# streams_v05.net
KiCad netlist of a schematic drawn in EAGLE
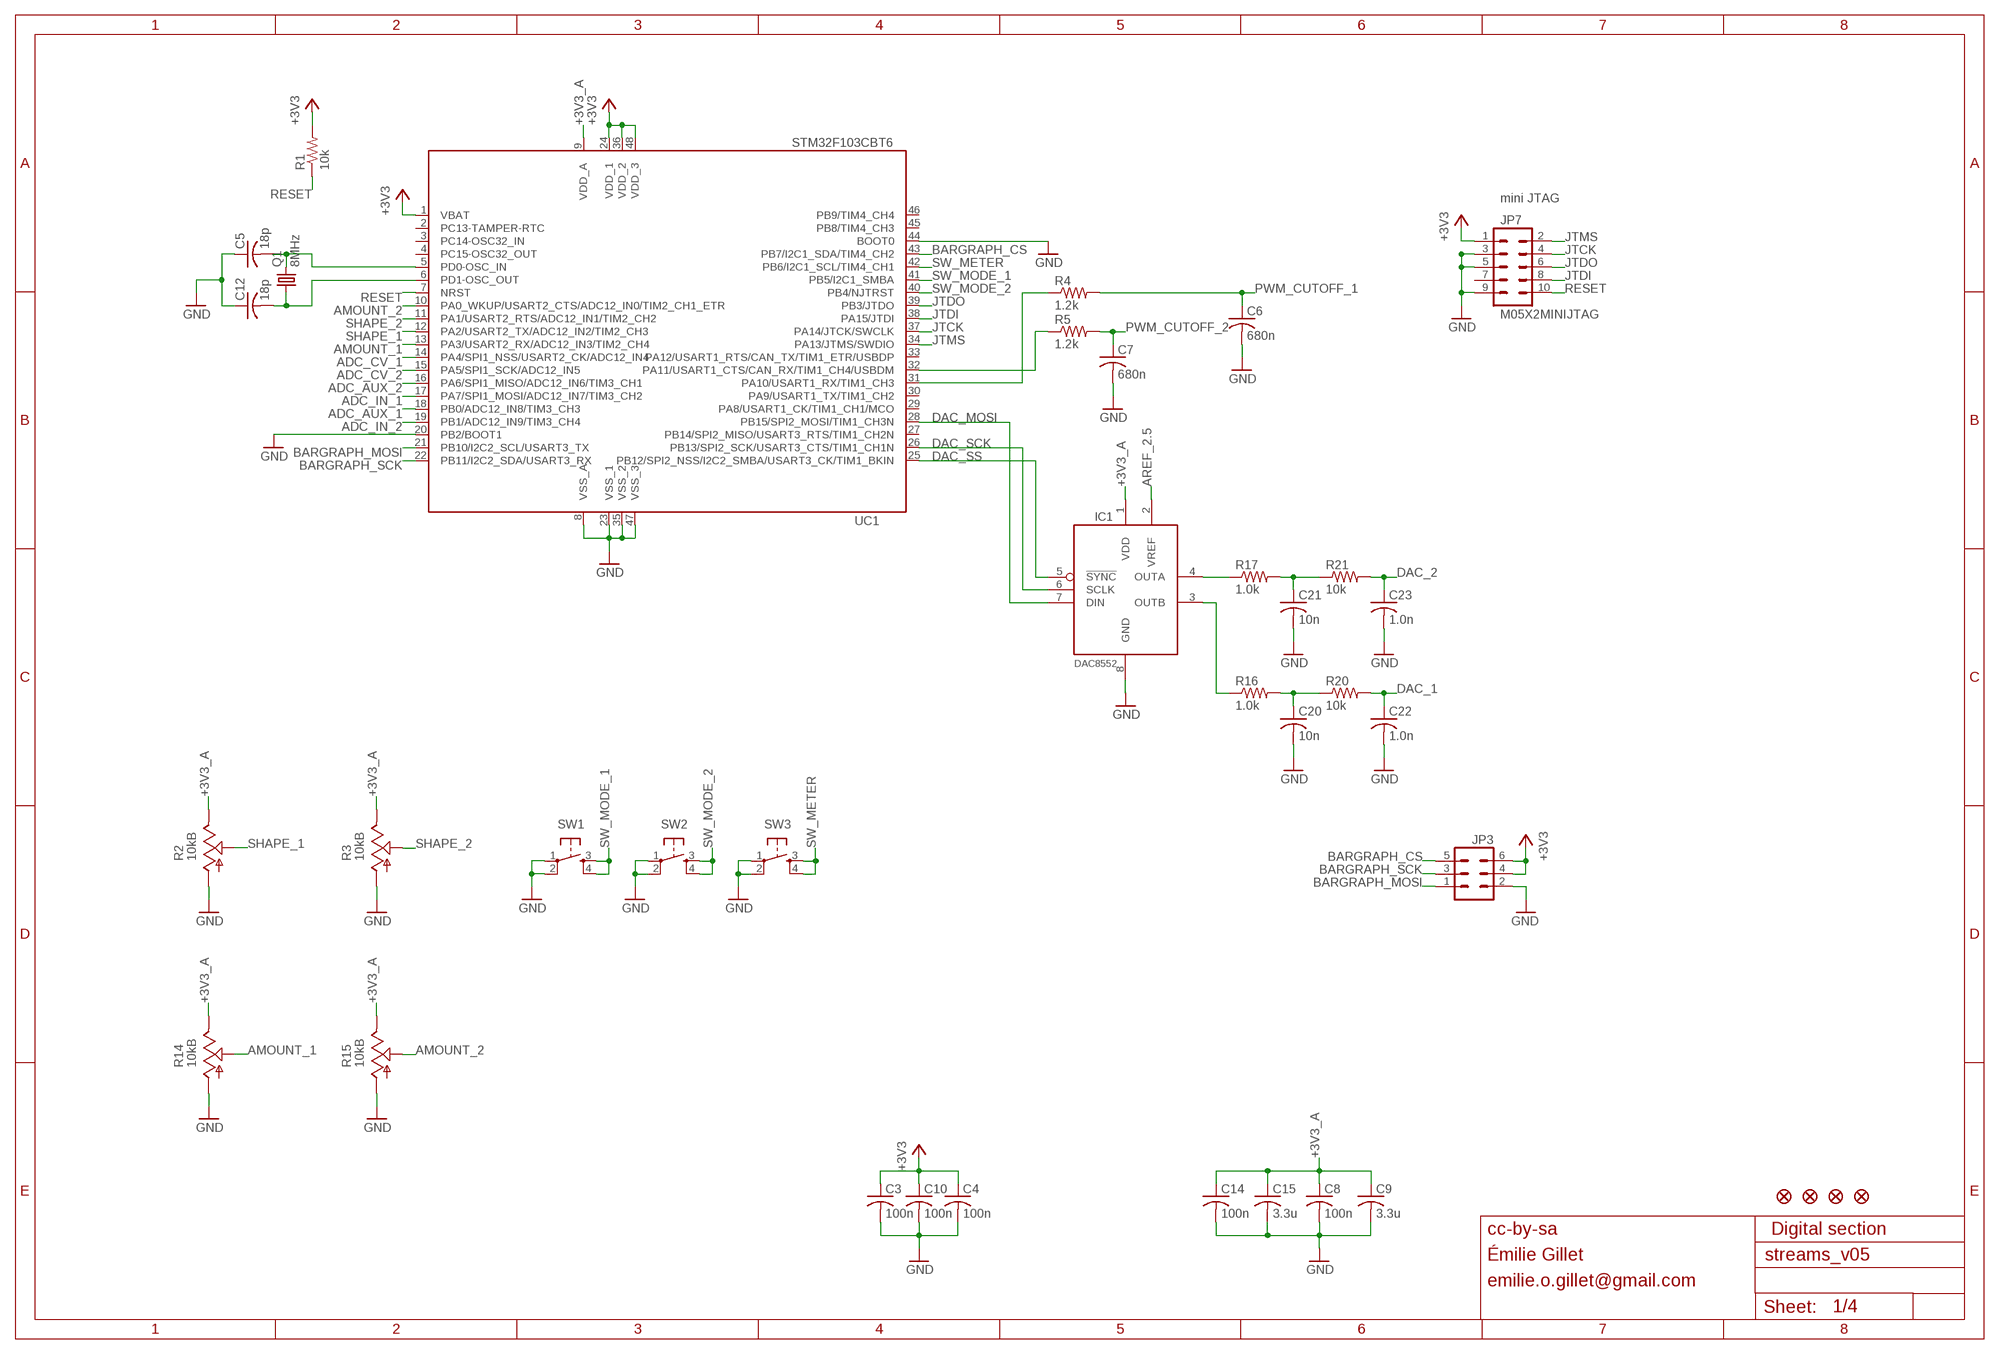
[diagram p0: schematic, sheet 1]
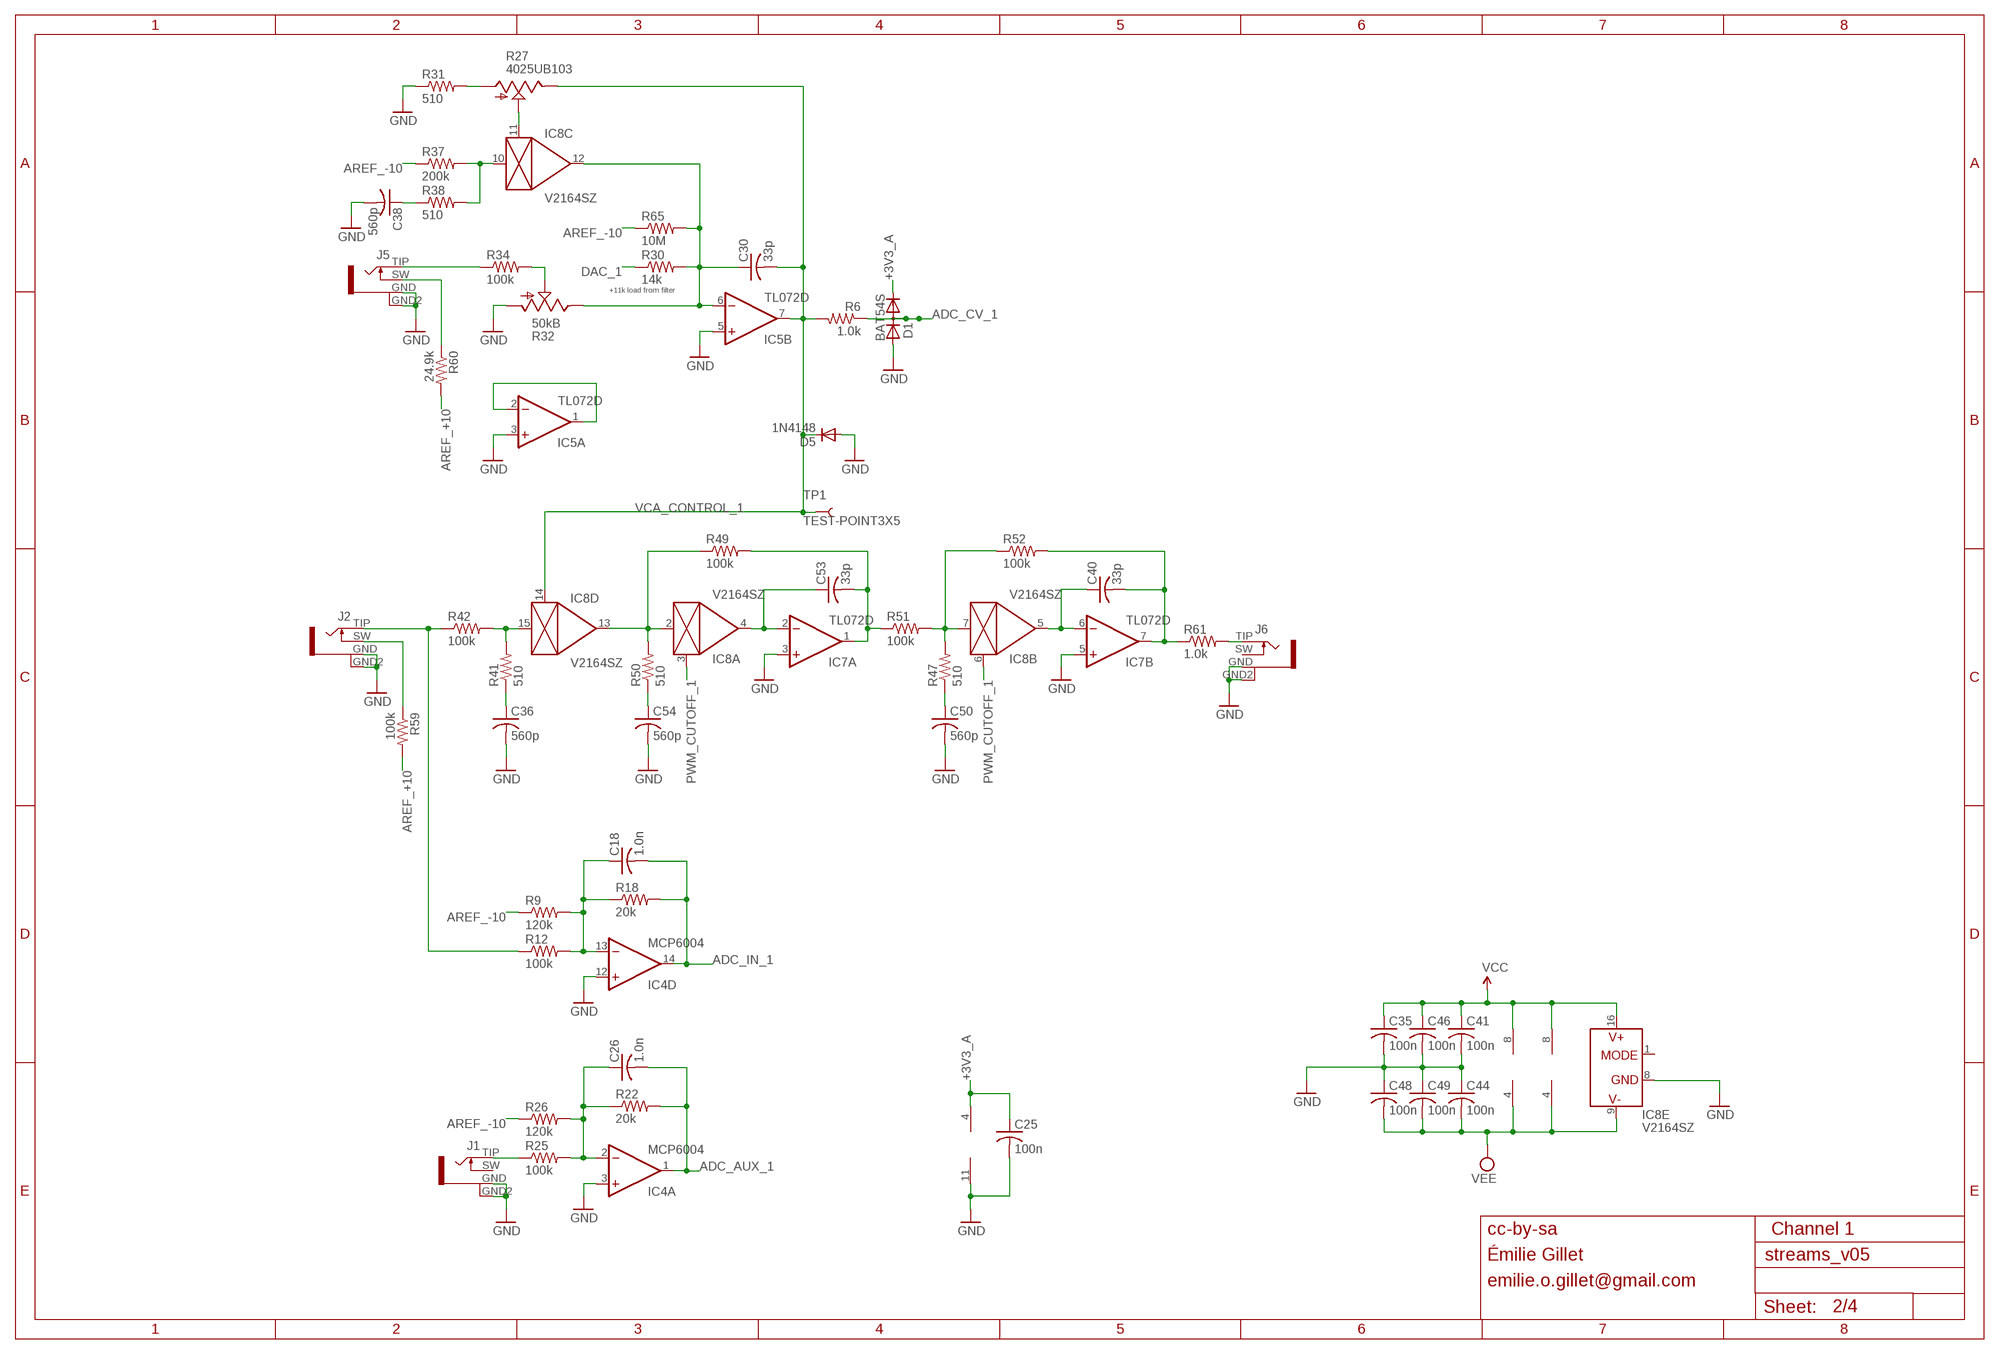
[diagram p1: schematic, sheet 2]
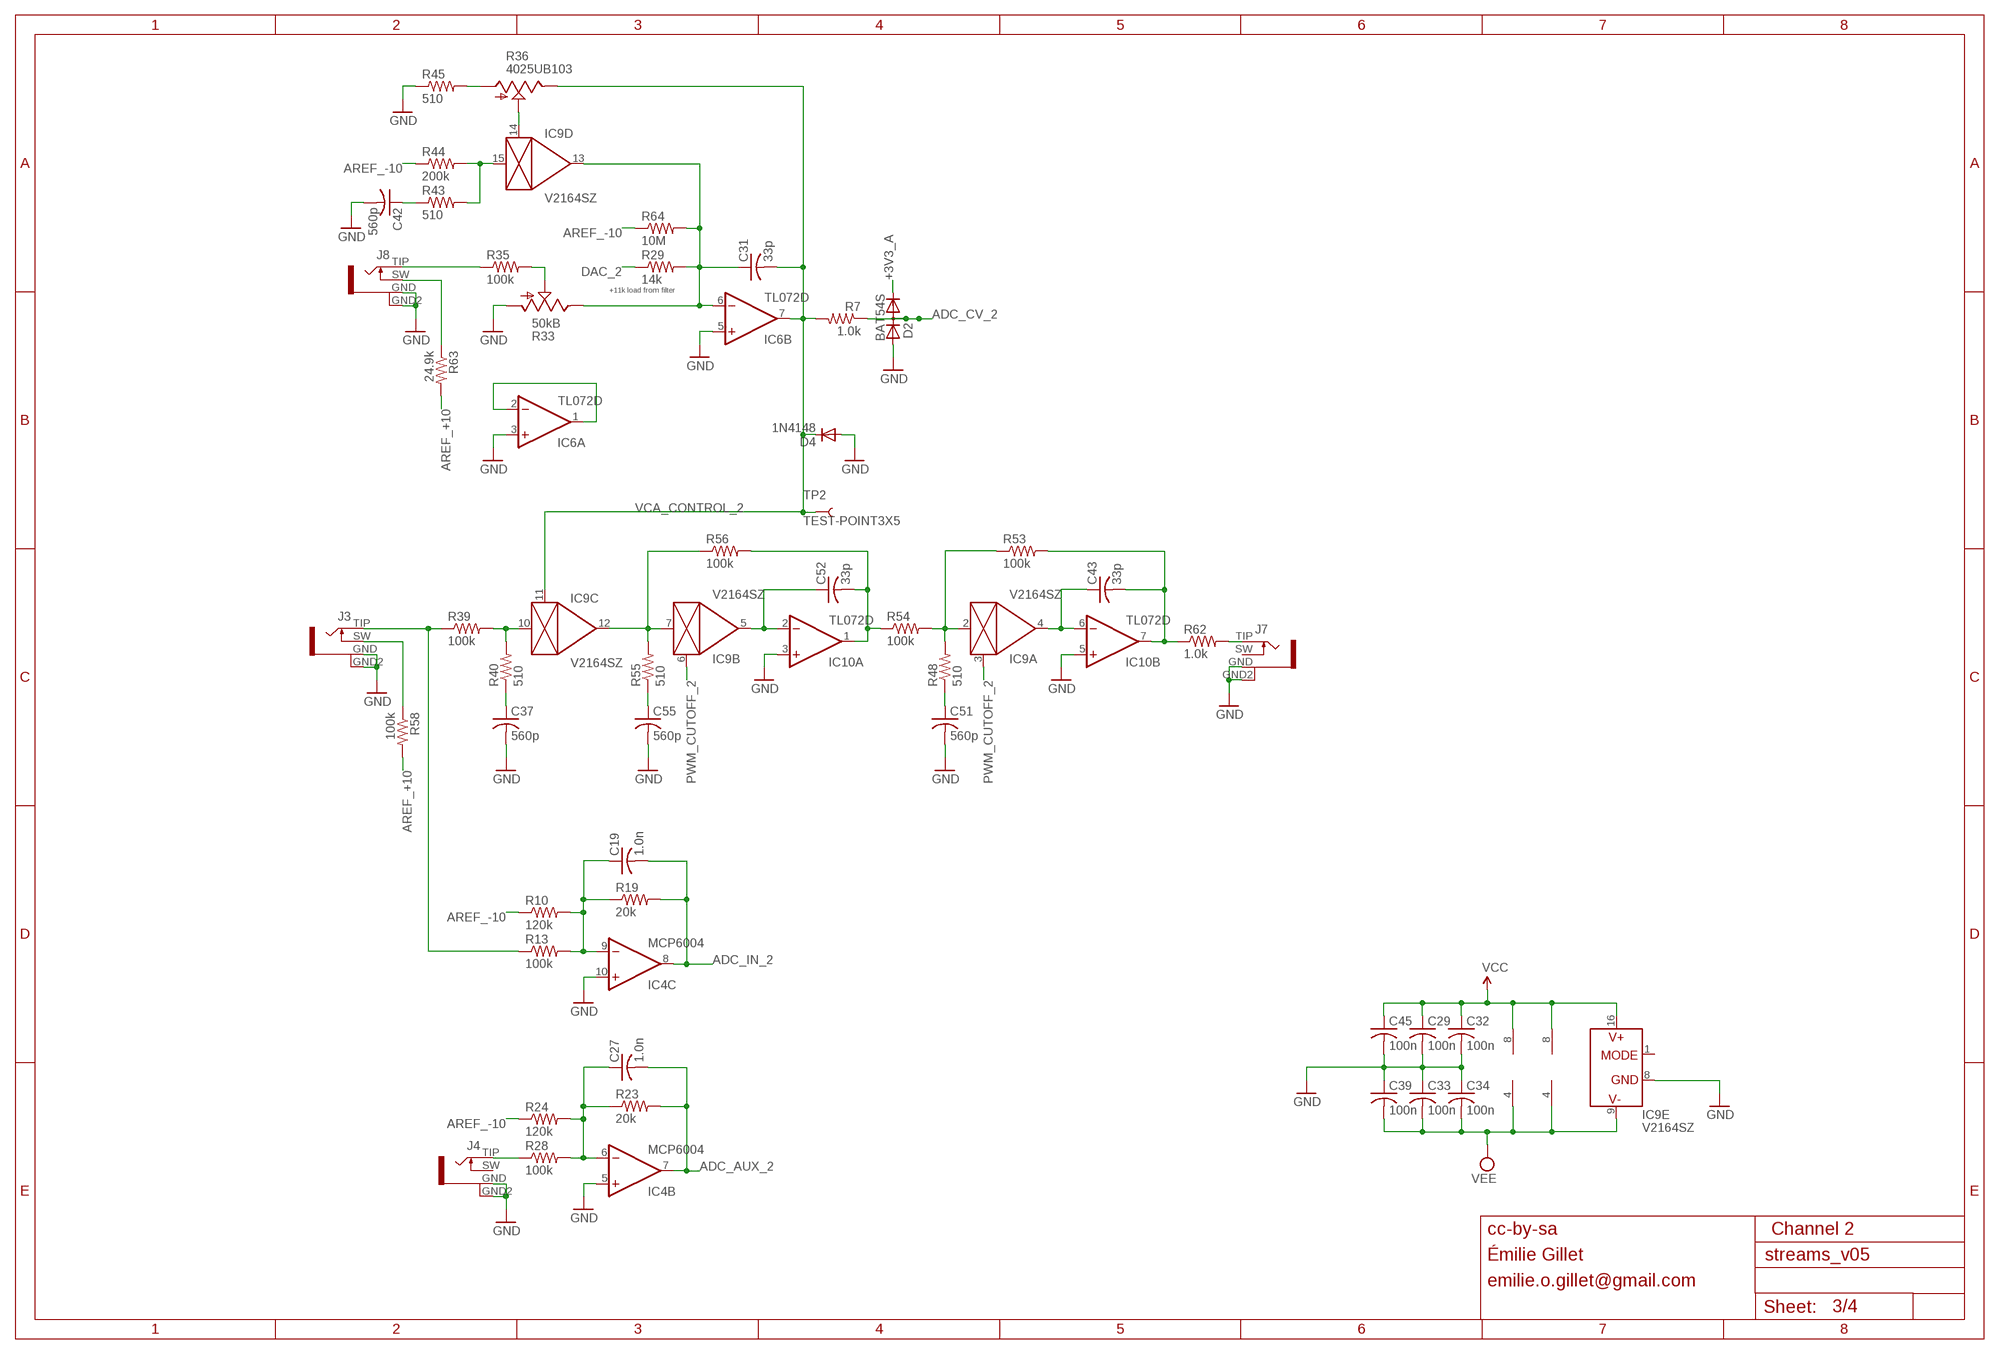
[diagram p2: schematic, sheet 3]
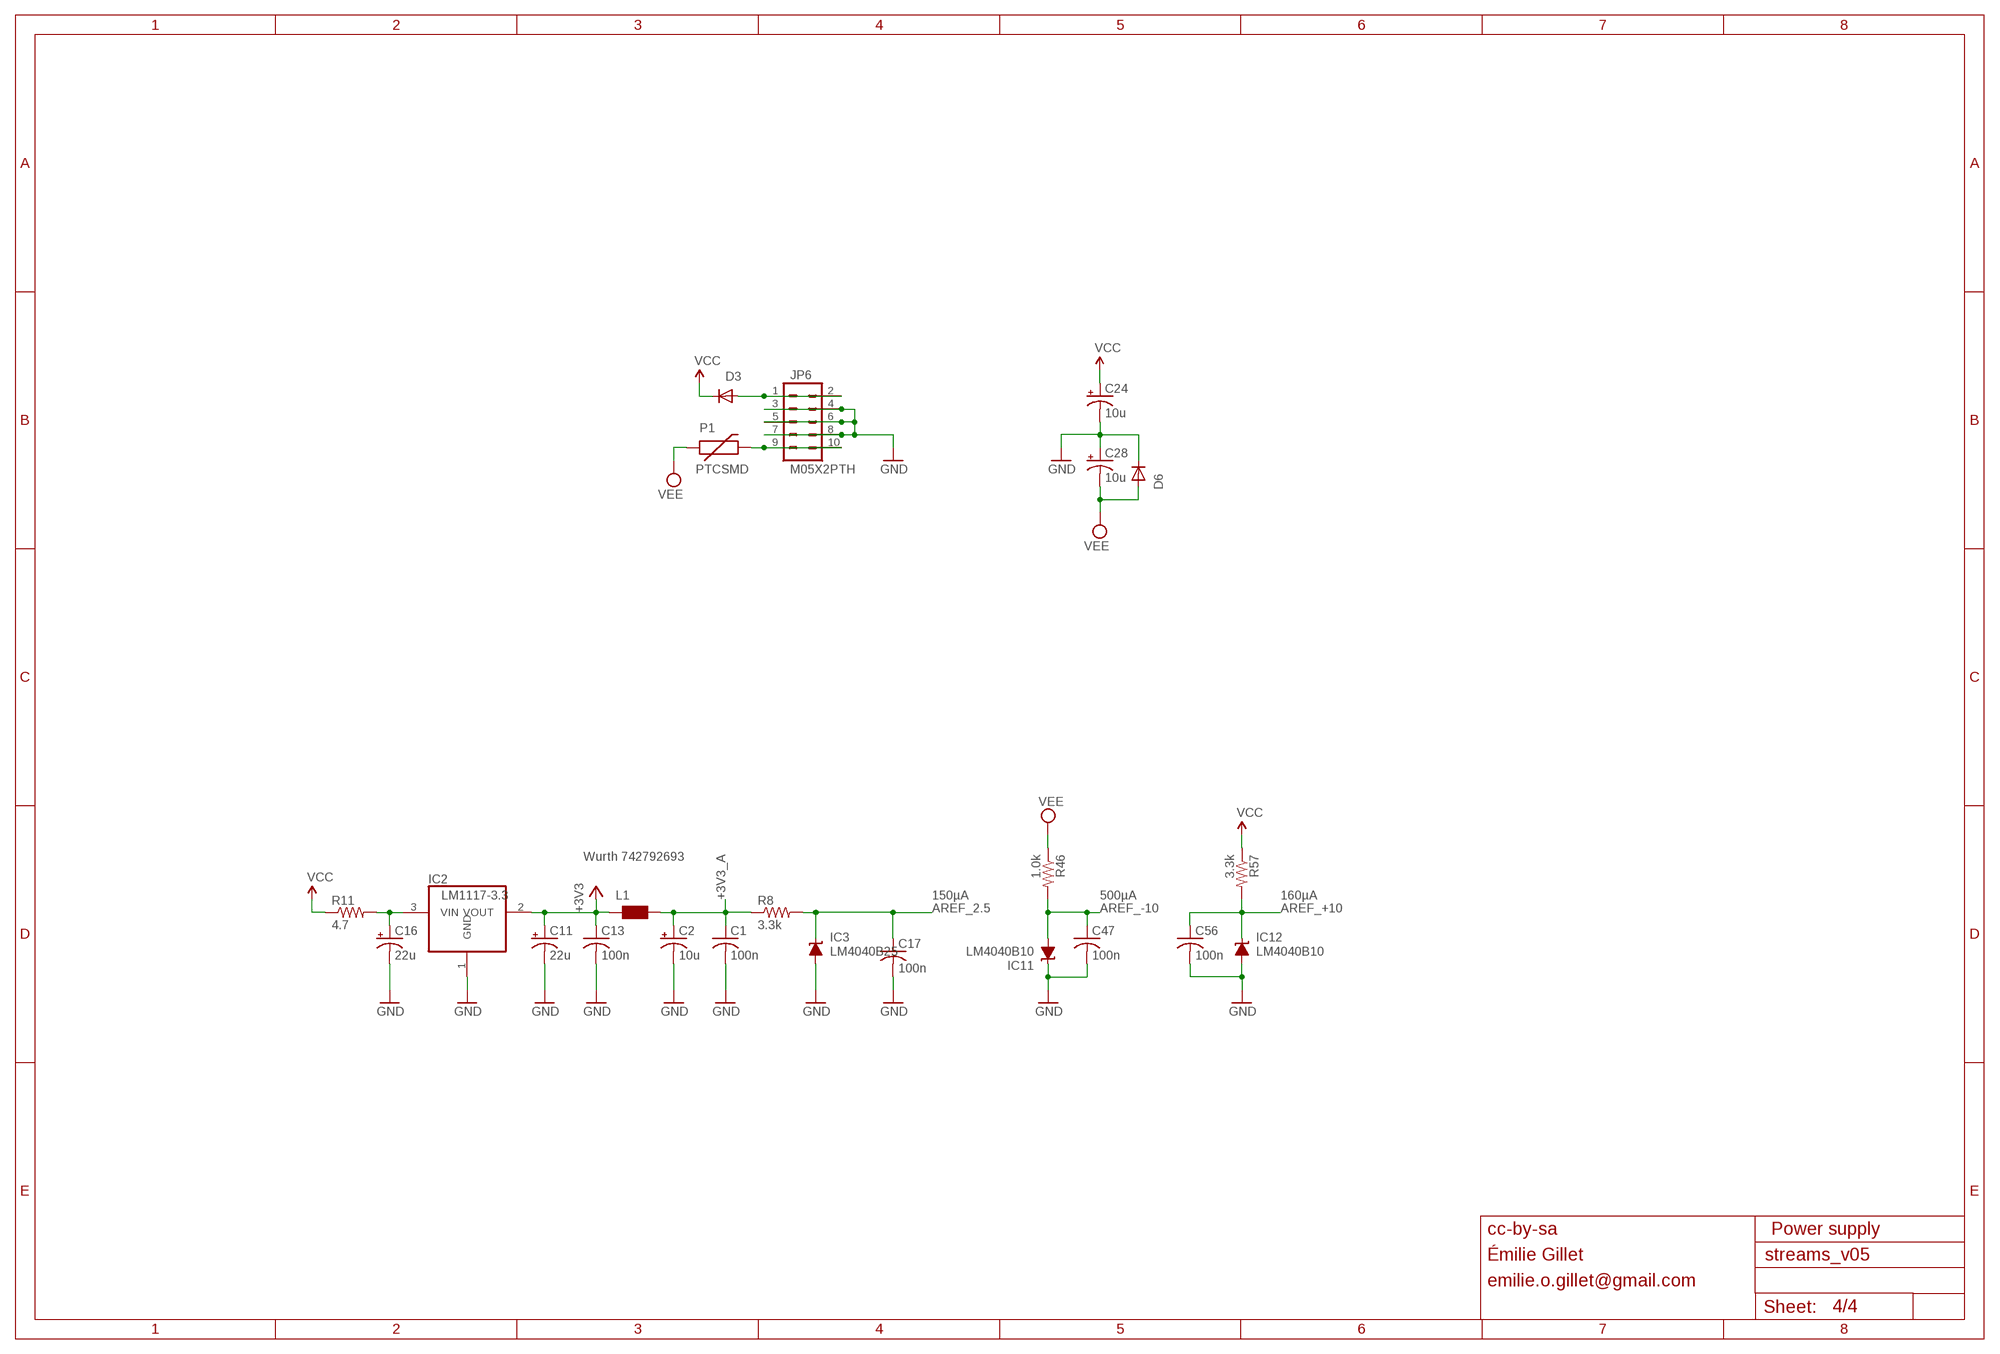
[diagram p3: schematic, sheet 4]

(export (version "E")
  (design (tool "Eeschema 10.0.6"))
  (components
    (comp (ref "C18")
      (value "1.0n")
      (footprint "eagle-import:C0603")
      (libsource (lib "eagle-import") (part "C-USC0603"))
    )
    (comp (ref "C25")
      (value "100n")
      (footprint "eagle-import:C0603")
      (libsource (lib "eagle-import") (part "C-USC0603"))
    )
    (comp (ref "C26")
      (value "1.0n")
      (footprint "eagle-import:C0603")
      (libsource (lib "eagle-import") (part "C-USC0603"))
    )
    (comp (ref "C30")
      (value "33p")
      (footprint "eagle-import:C0603")
      (libsource (lib "eagle-import") (part "C-USC0603"))
    )
    (comp (ref "C35")
      (value "100n")
      (footprint "eagle-import:C0603")
      (libsource (lib "eagle-import") (part "C-USC0603"))
    )
    (comp (ref "C36")
      (value "560p")
      (footprint "eagle-import:C0603")
      (libsource (lib "eagle-import") (part "C-USC0603"))
    )
    (comp (ref "C38")
      (value "560p")
      (footprint "eagle-import:C0603")
      (libsource (lib "eagle-import") (part "C-USC0603"))
    )
    (comp (ref "C40")
      (value "33p")
      (footprint "eagle-import:C0603")
      (libsource (lib "eagle-import") (part "C-USC0603"))
    )
    (comp (ref "C41")
      (value "100n")
      (footprint "eagle-import:C0603")
      (libsource (lib "eagle-import") (part "C-USC0603"))
    )
    (comp (ref "C44")
      (value "100n")
      (footprint "eagle-import:C0603")
      (libsource (lib "eagle-import") (part "C-USC0603"))
    )
    (comp (ref "C46")
      (value "100n")
      (footprint "eagle-import:C0603")
      (libsource (lib "eagle-import") (part "C-USC0603"))
    )
    (comp (ref "C48")
      (value "100n")
      (footprint "eagle-import:C0603")
      (libsource (lib "eagle-import") (part "C-USC0603"))
    )
    (comp (ref "C49")
      (value "100n")
      (footprint "eagle-import:C0603")
      (libsource (lib "eagle-import") (part "C-USC0603"))
    )
    (comp (ref "C50")
      (value "560p")
      (footprint "eagle-import:C0603")
      (libsource (lib "eagle-import") (part "C-USC0603"))
    )
    (comp (ref "C53")
      (value "33p")
      (footprint "eagle-import:C0603")
      (libsource (lib "eagle-import") (part "C-USC0603"))
    )
    (comp (ref "C54")
      (value "560p")
      (footprint "eagle-import:C0603")
      (libsource (lib "eagle-import") (part "C-USC0603"))
    )
    (comp (ref "D1")
      (value "BAT54S")
      (footprint "eagle-import:SOT23")
      (libsource (lib "eagle-import") (part "DIODE_2CACA-SOT23"))
    )
    (comp (ref "D5")
      (value "1N4148")
      (footprint "eagle-import:SOD323-W")
      (libsource (lib "eagle-import") (part "DIODE-SOD323-W"))
    )
    (comp (ref "IC4")
      (value "MCP6004")
      (footprint "eagle-import:SO14")
      (libsource (lib "eagle-import") (part "TL074D"))
    )
    (comp (ref "IC5")
      (value "TL072D")
      (footprint "eagle-import:SO08")
      (libsource (lib "eagle-import") (part "TL072D"))
    )
    (comp (ref "IC7")
      (value "TL072D")
      (footprint "eagle-import:SO08")
      (libsource (lib "eagle-import") (part "TL072D"))
    )
    (comp (ref "IC8")
      (value "V2164SZ")
      (footprint "eagle-import:SOIC16N")
      (libsource (lib "eagle-import") (part "SSM2164S"))
    )
    (comp (ref "J1")
      (value "PJ301WQP")
      (footprint "eagle-import:WQP_PJ_301BM_WIDER")
      (libsource (lib "eagle-import") (part "PJ301WQP"))
    )
    (comp (ref "J2")
      (value "PJ301WQP")
      (footprint "eagle-import:WQP_PJ_301BM_WIDER")
      (libsource (lib "eagle-import") (part "PJ301WQP"))
    )
    (comp (ref "J5")
      (value "PJ301WQP")
      (footprint "eagle-import:WQP_PJ_301BM_WIDER")
      (libsource (lib "eagle-import") (part "PJ301WQP"))
    )
    (comp (ref "J6")
      (value "PJ301WQP")
      (footprint "eagle-import:WQP_PJ_301BM_WIDER")
      (libsource (lib "eagle-import") (part "PJ301WQP"))
    )
    (comp (ref "R6")
      (value "1.0k")
      (footprint "eagle-import:R0603")
      (libsource (lib "eagle-import") (part "R-US_R0603"))
    )
    (comp (ref "R9")
      (value "120k")
      (footprint "eagle-import:R0603")
      (libsource (lib "eagle-import") (part "R-US_R0603"))
    )
    (comp (ref "R12")
      (value "100k")
      (footprint "eagle-import:R0603")
      (libsource (lib "eagle-import") (part "R-US_R0603"))
    )
    (comp (ref "R18")
      (value "20k")
      (footprint "eagle-import:R0603")
      (libsource (lib "eagle-import") (part "R-US_R0603"))
    )
    (comp (ref "R22")
      (value "20k")
      (footprint "eagle-import:R0603")
      (libsource (lib "eagle-import") (part "R-US_R0603"))
    )
    (comp (ref "R25")
      (value "100k")
      (footprint "eagle-import:R0603")
      (libsource (lib "eagle-import") (part "R-US_R0603"))
    )
    (comp (ref "R26")
      (value "120k")
      (footprint "eagle-import:R0603")
      (libsource (lib "eagle-import") (part "R-US_R0603"))
    )
    (comp (ref "R27")
      (value "4025UB103")
      (footprint "eagle-import:ALPS_POT_VERTICAL")
      (libsource (lib "eagle-import") (part "POT_USVERTICAL"))
    )
    (comp (ref "R30")
      (value "14k")
      (footprint "eagle-import:R0603")
      (libsource (lib "eagle-import") (part "R-US_R0603"))
    )
    (comp (ref "R31")
      (value "510")
      (footprint "eagle-import:R0603")
      (libsource (lib "eagle-import") (part "R-US_R0603"))
    )
    (comp (ref "R32")
      (value "50kB")
      (footprint "eagle-import:ALPS_POT_VERTICAL_PS")
      (libsource (lib "eagle-import") (part "POT_USVERTICAL_PS"))
    )
    (comp (ref "R34")
      (value "100k")
      (footprint "eagle-import:R0603")
      (libsource (lib "eagle-import") (part "R-US_R0603"))
    )
    (comp (ref "R37")
      (value "200k")
      (footprint "eagle-import:R0603")
      (libsource (lib "eagle-import") (part "R-US_R0603"))
    )
    (comp (ref "R38")
      (value "510")
      (footprint "eagle-import:R0603")
      (libsource (lib "eagle-import") (part "R-US_R0603"))
    )
    (comp (ref "R41")
      (value "510")
      (footprint "eagle-import:R0603")
      (libsource (lib "eagle-import") (part "R-US_R0603"))
    )
    (comp (ref "R42")
      (value "100k")
      (footprint "eagle-import:R0603")
      (libsource (lib "eagle-import") (part "R-US_R0603"))
    )
    (comp (ref "R47")
      (value "510")
      (footprint "eagle-import:R0603")
      (libsource (lib "eagle-import") (part "R-US_R0603"))
    )
    (comp (ref "R49")
      (value "100k")
      (footprint "eagle-import:R0603")
      (libsource (lib "eagle-import") (part "R-US_R0603"))
    )
    (comp (ref "R50")
      (value "510")
      (footprint "eagle-import:R0603")
      (libsource (lib "eagle-import") (part "R-US_R0603"))
    )
    (comp (ref "R51")
      (value "100k")
      (footprint "eagle-import:R0603")
      (libsource (lib "eagle-import") (part "R-US_R0603"))
    )
    (comp (ref "R52")
      (value "100k")
      (footprint "eagle-import:R0603")
      (libsource (lib "eagle-import") (part "R-US_R0603"))
    )
    (comp (ref "R59")
      (value "100k")
      (footprint "eagle-import:R0603")
      (libsource (lib "eagle-import") (part "R-US_R0603"))
    )
    (comp (ref "R60")
      (value "24.9k")
      (footprint "eagle-import:R0603")
      (libsource (lib "eagle-import") (part "R-US_R0603"))
    )
    (comp (ref "R61")
      (value "1.0k")
      (footprint "eagle-import:R0603")
      (libsource (lib "eagle-import") (part "R-US_R0603"))
    )
    (comp (ref "R65")
      (value "10M")
      (footprint "eagle-import:R0603")
      (libsource (lib "eagle-import") (part "R-US_R0603"))
    )
    (comp (ref "TP1")
      (value "TEST-POINT3X5")
      (footprint "eagle-import:PAD.03X.05")
      (libsource (lib "eagle-import") (part "TEST-POINT3X5"))
    )
    (comp (ref "C3")
      (value "100n")
      (footprint "eagle-import:C0603")
      (libsource (lib "eagle-import") (part "C-USC0603"))
    )
    (comp (ref "C4")
      (value "100n")
      (footprint "eagle-import:C0603")
      (libsource (lib "eagle-import") (part "C-USC0603"))
    )
    (comp (ref "C5")
      (value "18p")
      (footprint "eagle-import:C0603")
      (libsource (lib "eagle-import") (part "C-USC0603"))
    )
    (comp (ref "C6")
      (value "680n")
      (footprint "eagle-import:C0603")
      (libsource (lib "eagle-import") (part "C-USC0603"))
    )
    (comp (ref "C7")
      (value "680n")
      (footprint "eagle-import:C0603")
      (libsource (lib "eagle-import") (part "C-USC0603"))
    )
    (comp (ref "C8")
      (value "100n")
      (footprint "eagle-import:C0603")
      (libsource (lib "eagle-import") (part "C-USC0603"))
    )
    (comp (ref "C9")
      (value "3.3u")
      (footprint "eagle-import:C0603")
      (libsource (lib "eagle-import") (part "C-USC0603"))
    )
    (comp (ref "C10")
      (value "100n")
      (footprint "eagle-import:C0603")
      (libsource (lib "eagle-import") (part "C-USC0603"))
    )
    (comp (ref "C12")
      (value "18p")
      (footprint "eagle-import:C0603")
      (libsource (lib "eagle-import") (part "C-USC0603"))
    )
    (comp (ref "C14")
      (value "100n")
      (footprint "eagle-import:C0603")
      (libsource (lib "eagle-import") (part "C-USC0603"))
    )
    (comp (ref "C15")
      (value "3.3u")
      (footprint "eagle-import:C0603")
      (libsource (lib "eagle-import") (part "C-USC0603"))
    )
    (comp (ref "C20")
      (value "10n")
      (footprint "eagle-import:C0603")
      (libsource (lib "eagle-import") (part "C-USC0603"))
    )
    (comp (ref "C21")
      (value "10n")
      (footprint "eagle-import:C0603")
      (libsource (lib "eagle-import") (part "C-USC0603"))
    )
    (comp (ref "C22")
      (value "1.0n")
      (footprint "eagle-import:C0603")
      (libsource (lib "eagle-import") (part "C-USC0603"))
    )
    (comp (ref "C23")
      (value "1.0n")
      (footprint "eagle-import:C0603")
      (libsource (lib "eagle-import") (part "C-USC0603"))
    )
    (comp (ref "IC1")
      (value "DAC8552")
      (footprint "eagle-import:MSOP-8")
      (libsource (lib "eagle-import") (part "DAC8552"))
    )
    (comp (ref "JP1")
      (value "FIDUCIAL1X2")
      (footprint "eagle-import:FIDUCIAL-1X2")
      (libsource (lib "eagle-import") (part "FIDUCIAL1X2"))
    )
    (comp (ref "JP2")
      (value "FIDUCIAL1X2")
      (footprint "eagle-import:FIDUCIAL-1X2")
      (libsource (lib "eagle-import") (part "FIDUCIAL1X2"))
    )
    (comp (ref "JP3")
      (value "M03X2BOTTOM")
      (footprint "eagle-import:2X3_BOTTOM")
      (libsource (lib "eagle-import") (part "M03X2BOTTOM"))
    )
    (comp (ref "JP4")
      (value "FIDUCIAL1X2")
      (footprint "eagle-import:FIDUCIAL-1X2")
      (libsource (lib "eagle-import") (part "FIDUCIAL1X2"))
    )
    (comp (ref "JP5")
      (value "FIDUCIAL1X2")
      (footprint "eagle-import:FIDUCIAL-1X2")
      (libsource (lib "eagle-import") (part "FIDUCIAL1X2"))
    )
    (comp (ref "JP7")
      (value "M05X2MINIJTAG")
      (footprint "eagle-import:2X5-1.27")
      (libsource (lib "eagle-import") (part "M05X2MINIJTAG"))
    )
    (comp (ref "Q1")
      (value "8MHz")
      (footprint "eagle-import:HC49UP")
      (libsource (lib "eagle-import") (part "CRYSTALHC49UP"))
    )
    (comp (ref "R1")
      (value "10k")
      (footprint "eagle-import:R0603")
      (libsource (lib "eagle-import") (part "R-US_R0603"))
    )
    (comp (ref "R2")
      (value "10kB")
      (footprint "eagle-import:ALPS_POT_VERTICAL_PS")
      (libsource (lib "eagle-import") (part "POT_USVERTICAL_PS"))
    )
    (comp (ref "R3")
      (value "10kB")
      (footprint "eagle-import:ALPS_POT_VERTICAL_PS")
      (libsource (lib "eagle-import") (part "POT_USVERTICAL_PS"))
    )
    (comp (ref "R4")
      (value "1.2k")
      (footprint "eagle-import:R0603")
      (libsource (lib "eagle-import") (part "R-US_R0603"))
    )
    (comp (ref "R5")
      (value "1.2k")
      (footprint "eagle-import:R0603")
      (libsource (lib "eagle-import") (part "R-US_R0603"))
    )
    (comp (ref "R14")
      (value "10kB")
      (footprint "eagle-import:ALPS_POT_VERTICAL_PS")
      (libsource (lib "eagle-import") (part "POT_USVERTICAL_PS"))
    )
    (comp (ref "R15")
      (value "10kB")
      (footprint "eagle-import:ALPS_POT_VERTICAL_PS")
      (libsource (lib "eagle-import") (part "POT_USVERTICAL_PS"))
    )
    (comp (ref "R16")
      (value "1.0k")
      (footprint "eagle-import:R0603")
      (libsource (lib "eagle-import") (part "R-US_R0603"))
    )
    (comp (ref "R17")
      (value "1.0k")
      (footprint "eagle-import:R0603")
      (libsource (lib "eagle-import") (part "R-US_R0603"))
    )
    (comp (ref "R20")
      (value "10k")
      (footprint "eagle-import:R0603")
      (libsource (lib "eagle-import") (part "R-US_R0603"))
    )
    (comp (ref "R21")
      (value "10k")
      (footprint "eagle-import:R0603")
      (libsource (lib "eagle-import") (part "R-US_R0603"))
    )
    (comp (ref "SW1")
      (value "TAC_SWITCHPTH")
      (footprint "eagle-import:TACTILE-PTH")
      (libsource (lib "eagle-import") (part "TAC_SWITCHPTH"))
    )
    (comp (ref "SW2")
      (value "TAC_SWITCHPTH")
      (footprint "eagle-import:TACTILE-PTH")
      (libsource (lib "eagle-import") (part "TAC_SWITCHPTH"))
    )
    (comp (ref "SW3")
      (value "TAC_SWITCHPTH")
      (footprint "eagle-import:TACTILE-PTH")
      (libsource (lib "eagle-import") (part "TAC_SWITCHPTH"))
    )
    (comp (ref "UC1")
      (value "STM32F103CBT6")
      (footprint "eagle-import:LQFP48")
      (libsource (lib "eagle-import") (part "STM32F103CB"))
    )
    (comp (ref "C19")
      (value "1.0n")
      (footprint "eagle-import:C0603")
      (libsource (lib "eagle-import") (part "C-USC0603"))
    )
    (comp (ref "C27")
      (value "1.0n")
      (footprint "eagle-import:C0603")
      (libsource (lib "eagle-import") (part "C-USC0603"))
    )
    (comp (ref "C29")
      (value "100n")
      (footprint "eagle-import:C0603")
      (libsource (lib "eagle-import") (part "C-USC0603"))
    )
    (comp (ref "C31")
      (value "33p")
      (footprint "eagle-import:C0603")
      (libsource (lib "eagle-import") (part "C-USC0603"))
    )
    (comp (ref "C32")
      (value "100n")
      (footprint "eagle-import:C0603")
      (libsource (lib "eagle-import") (part "C-USC0603"))
    )
    (comp (ref "C33")
      (value "100n")
      (footprint "eagle-import:C0603")
      (libsource (lib "eagle-import") (part "C-USC0603"))
    )
    (comp (ref "C34")
      (value "100n")
      (footprint "eagle-import:C0603")
      (libsource (lib "eagle-import") (part "C-USC0603"))
    )
    (comp (ref "C37")
      (value "560p")
      (footprint "eagle-import:C0603")
      (libsource (lib "eagle-import") (part "C-USC0603"))
    )
    (comp (ref "C39")
      (value "100n")
      (footprint "eagle-import:C0603")
      (libsource (lib "eagle-import") (part "C-USC0603"))
    )
    (comp (ref "C42")
      (value "560p")
      (footprint "eagle-import:C0603")
      (libsource (lib "eagle-import") (part "C-USC0603"))
    )
    (comp (ref "C43")
      (value "33p")
      (footprint "eagle-import:C0603")
      (libsource (lib "eagle-import") (part "C-USC0603"))
    )
    (comp (ref "C45")
      (value "100n")
      (footprint "eagle-import:C0603")
      (libsource (lib "eagle-import") (part "C-USC0603"))
    )
    (comp (ref "C51")
      (value "560p")
      (footprint "eagle-import:C0603")
      (libsource (lib "eagle-import") (part "C-USC0603"))
    )
    (comp (ref "C52")
      (value "33p")
      (footprint "eagle-import:C0603")
      (libsource (lib "eagle-import") (part "C-USC0603"))
    )
    (comp (ref "C55")
      (value "560p")
      (footprint "eagle-import:C0603")
      (libsource (lib "eagle-import") (part "C-USC0603"))
    )
    (comp (ref "D2")
      (value "BAT54S")
      (footprint "eagle-import:SOT23")
      (libsource (lib "eagle-import") (part "DIODE_2CACA-SOT23"))
    )
    (comp (ref "D4")
      (value "1N4148")
      (footprint "eagle-import:SOD323-W")
      (libsource (lib "eagle-import") (part "DIODE-SOD323-W"))
    )
    (comp (ref "IC6")
      (value "TL072D")
      (footprint "eagle-import:SO08")
      (libsource (lib "eagle-import") (part "TL072D"))
    )
    (comp (ref "IC9")
      (value "V2164SZ")
      (footprint "eagle-import:SOIC16N")
      (libsource (lib "eagle-import") (part "SSM2164S"))
    )
    (comp (ref "IC10")
      (value "TL072D")
      (footprint "eagle-import:SO08")
      (libsource (lib "eagle-import") (part "TL072D"))
    )
    (comp (ref "J3")
      (value "PJ301WQP")
      (footprint "eagle-import:WQP_PJ_301BM_WIDER")
      (libsource (lib "eagle-import") (part "PJ301WQP"))
    )
    (comp (ref "J4")
      (value "PJ301WQP")
      (footprint "eagle-import:WQP_PJ_301BM_WIDER")
      (libsource (lib "eagle-import") (part "PJ301WQP"))
    )
    (comp (ref "J7")
      (value "PJ301WQP")
      (footprint "eagle-import:WQP_PJ_301BM_WIDER")
      (libsource (lib "eagle-import") (part "PJ301WQP"))
    )
    (comp (ref "J8")
      (value "PJ301WQP")
      (footprint "eagle-import:WQP_PJ_301BM_WIDER")
      (libsource (lib "eagle-import") (part "PJ301WQP"))
    )
    (comp (ref "R7")
      (value "1.0k")
      (footprint "eagle-import:R0603")
      (libsource (lib "eagle-import") (part "R-US_R0603"))
    )
    (comp (ref "R10")
      (value "120k")
      (footprint "eagle-import:R0603")
      (libsource (lib "eagle-import") (part "R-US_R0603"))
    )
    (comp (ref "R13")
      (value "100k")
      (footprint "eagle-import:R0603")
      (libsource (lib "eagle-import") (part "R-US_R0603"))
    )
    (comp (ref "R19")
      (value "20k")
      (footprint "eagle-import:R0603")
      (libsource (lib "eagle-import") (part "R-US_R0603"))
    )
    (comp (ref "R23")
      (value "20k")
      (footprint "eagle-import:R0603")
      (libsource (lib "eagle-import") (part "R-US_R0603"))
    )
    (comp (ref "R24")
      (value "120k")
      (footprint "eagle-import:R0603")
      (libsource (lib "eagle-import") (part "R-US_R0603"))
    )
    (comp (ref "R28")
      (value "100k")
      (footprint "eagle-import:R0603")
      (libsource (lib "eagle-import") (part "R-US_R0603"))
    )
    (comp (ref "R29")
      (value "14k")
      (footprint "eagle-import:R0603")
      (libsource (lib "eagle-import") (part "R-US_R0603"))
    )
    (comp (ref "R33")
      (value "50kB")
      (footprint "eagle-import:ALPS_POT_VERTICAL_PS")
      (libsource (lib "eagle-import") (part "POT_USVERTICAL_PS"))
    )
    (comp (ref "R35")
      (value "100k")
      (footprint "eagle-import:R0603")
      (libsource (lib "eagle-import") (part "R-US_R0603"))
    )
    (comp (ref "R36")
      (value "4025UB103")
      (footprint "eagle-import:ALPS_POT_VERTICAL")
      (libsource (lib "eagle-import") (part "POT_USVERTICAL"))
    )
    (comp (ref "R39")
      (value "100k")
      (footprint "eagle-import:R0603")
      (libsource (lib "eagle-import") (part "R-US_R0603"))
    )
    (comp (ref "R40")
      (value "510")
      (footprint "eagle-import:R0603")
      (libsource (lib "eagle-import") (part "R-US_R0603"))
    )
    (comp (ref "R43")
      (value "510")
      (footprint "eagle-import:R0603")
      (libsource (lib "eagle-import") (part "R-US_R0603"))
    )
    (comp (ref "R44")
      (value "200k")
      (footprint "eagle-import:R0603")
      (libsource (lib "eagle-import") (part "R-US_R0603"))
    )
    (comp (ref "R45")
      (value "510")
      (footprint "eagle-import:R0603")
      (libsource (lib "eagle-import") (part "R-US_R0603"))
    )
    (comp (ref "R48")
      (value "510")
      (footprint "eagle-import:R0603")
      (libsource (lib "eagle-import") (part "R-US_R0603"))
    )
    (comp (ref "R53")
      (value "100k")
      (footprint "eagle-import:R0603")
      (libsource (lib "eagle-import") (part "R-US_R0603"))
    )
    (comp (ref "R54")
      (value "100k")
      (footprint "eagle-import:R0603")
      (libsource (lib "eagle-import") (part "R-US_R0603"))
    )
    (comp (ref "R55")
      (value "510")
      (footprint "eagle-import:R0603")
      (libsource (lib "eagle-import") (part "R-US_R0603"))
    )
    (comp (ref "R56")
      (value "100k")
      (footprint "eagle-import:R0603")
      (libsource (lib "eagle-import") (part "R-US_R0603"))
    )
    (comp (ref "R58")
      (value "100k")
      (footprint "eagle-import:R0603")
      (libsource (lib "eagle-import") (part "R-US_R0603"))
    )
    (comp (ref "R62")
      (value "1.0k")
      (footprint "eagle-import:R0603")
      (libsource (lib "eagle-import") (part "R-US_R0603"))
    )
    (comp (ref "R63")
      (value "24.9k")
      (footprint "eagle-import:R0603")
      (libsource (lib "eagle-import") (part "R-US_R0603"))
    )
    (comp (ref "R64")
      (value "10M")
      (footprint "eagle-import:R0603")
      (libsource (lib "eagle-import") (part "R-US_R0603"))
    )
    (comp (ref "TP2")
      (value "TEST-POINT3X5")
      (footprint "eagle-import:PAD.03X.05")
      (libsource (lib "eagle-import") (part "TEST-POINT3X5"))
    )
    (comp (ref "C1")
      (value "100n")
      (footprint "eagle-import:C0603")
      (libsource (lib "eagle-import") (part "C-USC0603"))
    )
    (comp (ref "C2")
      (value "10u")
      (footprint "eagle-import:PANASONIC_B")
      (libsource (lib "eagle-import") (part "CPOL-USB"))
    )
    (comp (ref "C11")
      (value "22u")
      (footprint "eagle-import:PANASONIC_B")
      (libsource (lib "eagle-import") (part "CPOL-USB"))
    )
    (comp (ref "C13")
      (value "100n")
      (footprint "eagle-import:C0603")
      (libsource (lib "eagle-import") (part "C-USC0603"))
    )
    (comp (ref "C16")
      (value "22u")
      (footprint "eagle-import:PANASONIC_C")
      (libsource (lib "eagle-import") (part "CPOL-USC"))
    )
    (comp (ref "C17")
      (value "100n")
      (footprint "eagle-import:C0603")
      (libsource (lib "eagle-import") (part "C-USC0603"))
    )
    (comp (ref "C24")
      (value "10u")
      (footprint "eagle-import:PANASONIC_B")
      (libsource (lib "eagle-import") (part "CPOL-USB"))
    )
    (comp (ref "C28")
      (value "10u")
      (footprint "eagle-import:PANASONIC_B")
      (libsource (lib "eagle-import") (part "CPOL-USB"))
    )
    (comp (ref "C47")
      (value "100n")
      (footprint "eagle-import:C0603")
      (libsource (lib "eagle-import") (part "C-USC0603"))
    )
    (comp (ref "C56")
      (value "100n")
      (footprint "eagle-import:C0603")
      (libsource (lib "eagle-import") (part "C-USC0603"))
    )
    (comp (ref "D3")
      (value "1N5819HW")
      (footprint "eagle-import:SOD123")
      (libsource (lib "eagle-import") (part "DIODE-SOD123"))
    )
    (comp (ref "D6")
      (value "1N5819HW")
      (footprint "eagle-import:SOD123")
      (libsource (lib "eagle-import") (part "DIODE-SOD123"))
    )
    (comp (ref "IC2")
      (value "LM1117-3.3")
      (footprint "eagle-import:SOT223")
      (libsource (lib "eagle-import") (part "REG1117"))
    )
    (comp (ref "IC3")
      (value "LM4040B25")
      (footprint "eagle-import:DBZ_R-PDSO-G3")
      (libsource (lib "eagle-import") (part "LM4041DBZB12"))
    )
    (comp (ref "IC11")
      (value "LM4040B10")
      (footprint "eagle-import:DBZ_R-PDSO-G3")
      (libsource (lib "eagle-import") (part "LM4041DBZB12"))
    )
    (comp (ref "IC12")
      (value "LM4040B10")
      (footprint "eagle-import:DBZ_R-PDSO-G3")
      (libsource (lib "eagle-import") (part "LM4041DBZB12"))
    )
    (comp (ref "JP6")
      (value "M05X2PTH")
      (footprint "eagle-import:AVR_ICSP")
      (libsource (lib "eagle-import") (part "M05X2PTH"))
    )
    (comp (ref "L1")
      (value "WE-CBF_0603")
      (footprint "eagle-import:0603")
      (libsource (lib "eagle-import") (part "WE-CBF_0603"))
    )
    (comp (ref "P1")
      (value "PTCSMD")
      (footprint "eagle-import:PTC-1206")
      (libsource (lib "eagle-import") (part "PTCSMD"))
    )
    (comp (ref "R8")
      (value "3.3k")
      (footprint "eagle-import:R0603")
      (libsource (lib "eagle-import") (part "R-US_R0603"))
    )
    (comp (ref "R11")
      (value "4.7")
      (footprint "eagle-import:R1206")
      (libsource (lib "eagle-import") (part "R-US_R1206"))
    )
    (comp (ref "R46")
      (value "1.0k")
      (footprint "eagle-import:R0603")
      (libsource (lib "eagle-import") (part "R-US_R0603"))
    )
    (comp (ref "R57")
      (value "3.3k")
      (footprint "eagle-import:R0603")
      (libsource (lib "eagle-import") (part "R-US_R0603"))
    )
  )
  (nets
    (net (code "1") (name "+3V3") (class "Default")
      (node (ref "C10") (pin "1") (pinfunction "1_1") (pintype "passive"))
      (node (ref "C11") (pin "+") (pinfunction "+_+") (pintype "passive"))
      (node (ref "C13") (pin "1") (pinfunction "1_1") (pintype "passive"))
      (node (ref "C3") (pin "1") (pinfunction "1_1") (pintype "passive"))
      (node (ref "C4") (pin "1") (pinfunction "1_1") (pintype "passive"))
      (node (ref "IC2") (pin "2") (pinfunction "VOUT_2") (pintype "output"))
      (node (ref "JP3") (pin "4") (pinfunction "4_4") (pintype "passive"))
      (node (ref "JP3") (pin "6") (pinfunction "6_6") (pintype "passive"))
      (node (ref "JP7") (pin "1") (pinfunction "1_1") (pintype "passive"))
      (node (ref "L1") (pin "1") (pinfunction "1_1") (pintype "passive"))
      (node (ref "R1") (pin "2") (pinfunction "2_2") (pintype "passive"))
      (node (ref "UC1") (pin "1") (pinfunction "VBAT_1") (pintype "power_in"))
      (node (ref "UC1") (pin "24") (pinfunction "VDD_1_24") (pintype "power_in"))
      (node (ref "UC1") (pin "36") (pinfunction "VDD_2_36") (pintype "power_in"))
      (node (ref "UC1") (pin "48") (pinfunction "VDD_3_48") (pintype "power_in"))
    )
    (net (code "2") (name "+3V3_A") (class "Default")
      (node (ref "C1") (pin "1") (pinfunction "1_1") (pintype "passive"))
      (node (ref "C14") (pin "1") (pinfunction "1_1") (pintype "passive"))
      (node (ref "C15") (pin "1") (pinfunction "1_1") (pintype "passive"))
      (node (ref "C2") (pin "+") (pinfunction "+_+") (pintype "passive"))
      (node (ref "C25") (pin "1") (pinfunction "1_1") (pintype "passive"))
      (node (ref "C8") (pin "1") (pinfunction "1_1") (pintype "passive"))
      (node (ref "C9") (pin "1") (pinfunction "1_1") (pintype "passive"))
      (node (ref "D1") (pin "2") (pinfunction "C_2") (pintype "passive"))
      (node (ref "D2") (pin "2") (pinfunction "C_2") (pintype "passive"))
      (node (ref "IC1") (pin "1") (pinfunction "VDD_1") (pintype "power_in"))
      (node (ref "IC4") (pin "4") (pinfunction "V+_4") (pintype "power_in"))
      (node (ref "L1") (pin "2") (pinfunction "2_2") (pintype "passive"))
      (node (ref "R14") (pin "P$1") (pinfunction "E_P$1") (pintype "passive"))
      (node (ref "R15") (pin "P$1") (pinfunction "E_P$1") (pintype "passive"))
      (node (ref "R2") (pin "P$1") (pinfunction "E_P$1") (pintype "passive"))
      (node (ref "R3") (pin "P$1") (pinfunction "E_P$1") (pintype "passive"))
      (node (ref "R8") (pin "1") (pinfunction "1_1") (pintype "passive"))
      (node (ref "UC1") (pin "9") (pinfunction "VDD_A_9") (pintype "power_in"))
    )
    (net (code "3") (name "ADC_AUX_1") (class "Default")
      (node (ref "C26") (pin "2") (pinfunction "2_2") (pintype "passive"))
      (node (ref "IC4") (pin "1") (pinfunction "OUT_1") (pintype "output"))
      (node (ref "R22") (pin "2") (pinfunction "2_2") (pintype "passive"))
      (node (ref "UC1") (pin "18") (pinfunction "PB0/ADC12_IN8/TIM3_CH3_18") (pintype "bidirectional"))
    )
    (net (code "4") (name "ADC_AUX_2") (class "Default")
      (node (ref "C27") (pin "2") (pinfunction "2_2") (pintype "passive"))
      (node (ref "IC4") (pin "7") (pinfunction "OUT_7") (pintype "output"))
      (node (ref "R23") (pin "2") (pinfunction "2_2") (pintype "passive"))
      (node (ref "UC1") (pin "16") (pinfunction "PA6/SPI1_MISO/ADC12_IN6/TIM3_CH1_16") (pintype "bidirectional"))
    )
    (net (code "5") (name "ADC_CV_1") (class "Default")
      (node (ref "D1") (pin "3") (pinfunction "AC_3") (pintype "passive"))
      (node (ref "R6") (pin "1") (pinfunction "1_1") (pintype "passive"))
      (node (ref "UC1") (pin "14") (pinfunction "PA4/SPI1_NSS/USART2_CK/ADC12_IN4_14") (pintype "bidirectional"))
    )
    (net (code "6") (name "ADC_CV_2") (class "Default")
      (node (ref "D2") (pin "3") (pinfunction "AC_3") (pintype "passive"))
      (node (ref "R7") (pin "1") (pinfunction "1_1") (pintype "passive"))
      (node (ref "UC1") (pin "15") (pinfunction "PA5/SPI1_SCK/ADC12_IN5_15") (pintype "bidirectional"))
    )
    (net (code "7") (name "ADC_IN_1") (class "Default")
      (node (ref "C18") (pin "2") (pinfunction "2_2") (pintype "passive"))
      (node (ref "IC4") (pin "14") (pinfunction "OUT_14") (pintype "output"))
      (node (ref "R18") (pin "2") (pinfunction "2_2") (pintype "passive"))
      (node (ref "UC1") (pin "17") (pinfunction "PA7/SPI1_MOSI/ADC12_IN7/TIM3_CH2_17") (pintype "bidirectional"))
    )
    (net (code "8") (name "ADC_IN_2") (class "Default")
      (node (ref "C19") (pin "2") (pinfunction "2_2") (pintype "passive"))
      (node (ref "IC4") (pin "8") (pinfunction "OUT_8") (pintype "output"))
      (node (ref "R19") (pin "2") (pinfunction "2_2") (pintype "passive"))
      (node (ref "UC1") (pin "19") (pinfunction "PB1/ADC12_IN9/TIM3_CH4_19") (pintype "bidirectional"))
    )
    (net (code "9") (name "AMOUNT_1") (class "Default")
      (node (ref "R14") (pin "P$2") (pinfunction "S_P$2") (pintype "passive"))
      (node (ref "UC1") (pin "13") (pinfunction "PA3/USART2_RX/ADC12_IN3/TIM2_CH4_13") (pintype "bidirectional"))
    )
    (net (code "10") (name "AMOUNT_2") (class "Default")
      (node (ref "R15") (pin "P$2") (pinfunction "S_P$2") (pintype "passive"))
      (node (ref "UC1") (pin "10") (pinfunction "PA0_WKUP/USART2_CTS/ADC12_IN0/TIM2_CH1_ETR_10") (pintype "bidirectional"))
    )
    (net (code "11") (name "AREF_+10") (class "Default")
      (node (ref "C56") (pin "1") (pinfunction "1_1") (pintype "passive"))
      (node (ref "IC12") (pin "1") (pinfunction "C_1") (pintype "passive"))
      (node (ref "R57") (pin "2") (pinfunction "2_2") (pintype "passive"))
      (node (ref "R58") (pin "2") (pinfunction "2_2") (pintype "passive"))
      (node (ref "R59") (pin "2") (pinfunction "2_2") (pintype "passive"))
      (node (ref "R60") (pin "2") (pinfunction "2_2") (pintype "passive"))
      (node (ref "R63") (pin "2") (pinfunction "2_2") (pintype "passive"))
    )
    (net (code "12") (name "AREF_-10") (class "Default")
      (node (ref "C47") (pin "1") (pinfunction "1_1") (pintype "passive"))
      (node (ref "IC11") (pin "2") (pinfunction "A_2") (pintype "passive"))
      (node (ref "R10") (pin "1") (pinfunction "1_1") (pintype "passive"))
      (node (ref "R24") (pin "1") (pinfunction "1_1") (pintype "passive"))
      (node (ref "R26") (pin "1") (pinfunction "1_1") (pintype "passive"))
      (node (ref "R37") (pin "1") (pinfunction "1_1") (pintype "passive"))
      (node (ref "R44") (pin "1") (pinfunction "1_1") (pintype "passive"))
      (node (ref "R46") (pin "2") (pinfunction "2_2") (pintype "passive"))
      (node (ref "R64") (pin "1") (pinfunction "1_1") (pintype "passive"))
      (node (ref "R65") (pin "1") (pinfunction "1_1") (pintype "passive"))
      (node (ref "R9") (pin "1") (pinfunction "1_1") (pintype "passive"))
    )
    (net (code "13") (name "AREF_2.5") (class "Default")
      (node (ref "C17") (pin "1") (pinfunction "1_1") (pintype "passive"))
      (node (ref "IC1") (pin "2") (pinfunction "VREF_2") (pintype "power_in"))
      (node (ref "IC3") (pin "1") (pinfunction "C_1") (pintype "passive"))
      (node (ref "R8") (pin "2") (pinfunction "2_2") (pintype "passive"))
    )
    (net (code "14") (name "BARGRAPH_CS") (class "Default")
      (node (ref "JP3") (pin "5") (pinfunction "5_5") (pintype "passive"))
      (node (ref "UC1") (pin "43") (pinfunction "PB7/I2C1_SDA/TIM4_CH2_43") (pintype "bidirectional"))
    )
    (net (code "15") (name "BARGRAPH_MOSI") (class "Default")
      (node (ref "JP3") (pin "1") (pinfunction "1_1") (pintype "passive"))
      (node (ref "UC1") (pin "21") (pinfunction "PB10/I2C2_SCL/USART3_TX_21") (pintype "input"))
    )
    (net (code "16") (name "BARGRAPH_SCK") (class "Default")
      (node (ref "JP3") (pin "3") (pinfunction "3_3") (pintype "passive"))
      (node (ref "UC1") (pin "22") (pinfunction "PB11/I2C2_SDA/USART3_RX_22") (pintype "input"))
    )
    (net (code "17") (name "DAC_1") (class "Default")
      (node (ref "C22") (pin "1") (pinfunction "1_1") (pintype "passive"))
      (node (ref "R20") (pin "2") (pinfunction "2_2") (pintype "passive"))
      (node (ref "R30") (pin "1") (pinfunction "1_1") (pintype "passive"))
    )
    (net (code "18") (name "DAC_2") (class "Default")
      (node (ref "C23") (pin "1") (pinfunction "1_1") (pintype "passive"))
      (node (ref "R21") (pin "2") (pinfunction "2_2") (pintype "passive"))
      (node (ref "R29") (pin "1") (pinfunction "1_1") (pintype "passive"))
    )
    (net (code "19") (name "DAC_MOSI") (class "Default")
      (node (ref "IC1") (pin "7") (pinfunction "DIN_7") (pintype "bidirectional"))
      (node (ref "UC1") (pin "28") (pinfunction "PB15/SPI2_MOSI/TIM1_CH3N_28") (pintype "input"))
    )
    (net (code "20") (name "DAC_SCK") (class "Default")
      (node (ref "IC1") (pin "6") (pinfunction "SCLK_6") (pintype "bidirectional"))
      (node (ref "UC1") (pin "26") (pinfunction "PB13/SPI2_SCK/USART3_CTS/TIM1_CH1N_26") (pintype "input"))
    )
    (net (code "21") (name "DAC_SS") (class "Default")
      (node (ref "IC1") (pin "5") (pinfunction "~{SYNC}_5") (pintype "bidirectional"))
      (node (ref "UC1") (pin "25") (pinfunction "PB12/SPI2_NSS/I2C2_SMBA/USART3_CK/TIM1_BKIN_25") (pintype "input"))
    )
    (net (code "22") (name "GND") (class "Default")
      (node (ref "C1") (pin "2") (pinfunction "2_2") (pintype "passive"))
      (node (ref "C10") (pin "2") (pinfunction "2_2") (pintype "passive"))
      (node (ref "C11") (pin "-") (pinfunction "-_-") (pintype "passive"))
      (node (ref "C12") (pin "1") (pinfunction "1_1") (pintype "passive"))
      (node (ref "C13") (pin "2") (pinfunction "2_2") (pintype "passive"))
      (node (ref "C14") (pin "2") (pinfunction "2_2") (pintype "passive"))
      (node (ref "C15") (pin "2") (pinfunction "2_2") (pintype "passive"))
      (node (ref "C16") (pin "-") (pinfunction "-_-") (pintype "passive"))
      (node (ref "C17") (pin "2") (pinfunction "2_2") (pintype "passive"))
      (node (ref "C2") (pin "-") (pinfunction "-_-") (pintype "passive"))
      (node (ref "C20") (pin "2") (pinfunction "2_2") (pintype "passive"))
      (node (ref "C21") (pin "2") (pinfunction "2_2") (pintype "passive"))
      (node (ref "C22") (pin "2") (pinfunction "2_2") (pintype "passive"))
      (node (ref "C23") (pin "2") (pinfunction "2_2") (pintype "passive"))
      (node (ref "C24") (pin "-") (pinfunction "-_-") (pintype "passive"))
      (node (ref "C25") (pin "2") (pinfunction "2_2") (pintype "passive"))
      (node (ref "C28") (pin "+") (pinfunction "+_+") (pintype "passive"))
      (node (ref "C29") (pin "2") (pinfunction "2_2") (pintype "passive"))
      (node (ref "C3") (pin "2") (pinfunction "2_2") (pintype "passive"))
      (node (ref "C32") (pin "2") (pinfunction "2_2") (pintype "passive"))
      (node (ref "C33") (pin "1") (pinfunction "1_1") (pintype "passive"))
      (node (ref "C34") (pin "1") (pinfunction "1_1") (pintype "passive"))
      (node (ref "C35") (pin "2") (pinfunction "2_2") (pintype "passive"))
      (node (ref "C36") (pin "2") (pinfunction "2_2") (pintype "passive"))
      (node (ref "C37") (pin "2") (pinfunction "2_2") (pintype "passive"))
      (node (ref "C38") (pin "2") (pinfunction "2_2") (pintype "passive"))
      (node (ref "C39") (pin "1") (pinfunction "1_1") (pintype "passive"))
      (node (ref "C4") (pin "2") (pinfunction "2_2") (pintype "passive"))
      (node (ref "C41") (pin "2") (pinfunction "2_2") (pintype "passive"))
      (node (ref "C42") (pin "2") (pinfunction "2_2") (pintype "passive"))
      (node (ref "C44") (pin "1") (pinfunction "1_1") (pintype "passive"))
      (node (ref "C45") (pin "2") (pinfunction "2_2") (pintype "passive"))
      (node (ref "C46") (pin "2") (pinfunction "2_2") (pintype "passive"))
      (node (ref "C47") (pin "2") (pinfunction "2_2") (pintype "passive"))
      (node (ref "C48") (pin "1") (pinfunction "1_1") (pintype "passive"))
      (node (ref "C49") (pin "1") (pinfunction "1_1") (pintype "passive"))
      (node (ref "C5") (pin "1") (pinfunction "1_1") (pintype "passive"))
      (node (ref "C50") (pin "2") (pinfunction "2_2") (pintype "passive"))
      (node (ref "C51") (pin "2") (pinfunction "2_2") (pintype "passive"))
      (node (ref "C54") (pin "2") (pinfunction "2_2") (pintype "passive"))
      (node (ref "C55") (pin "2") (pinfunction "2_2") (pintype "passive"))
      (node (ref "C56") (pin "2") (pinfunction "2_2") (pintype "passive"))
      (node (ref "C6") (pin "2") (pinfunction "2_2") (pintype "passive"))
      (node (ref "C7") (pin "2") (pinfunction "2_2") (pintype "passive"))
      (node (ref "C8") (pin "2") (pinfunction "2_2") (pintype "passive"))
      (node (ref "C9") (pin "2") (pinfunction "2_2") (pintype "passive"))
      (node (ref "D1") (pin "1") (pinfunction "A_1") (pintype "passive"))
      (node (ref "D2") (pin "1") (pinfunction "A_1") (pintype "passive"))
      (node (ref "D4") (pin "A") (pinfunction "A_A") (pintype "passive"))
      (node (ref "D5") (pin "A") (pinfunction "A_A") (pintype "passive"))
      (node (ref "D6") (pin "C") (pinfunction "C_C") (pintype "passive"))
      (node (ref "IC1") (pin "8") (pinfunction "GND_8") (pintype "power_in"))
      (node (ref "IC10") (pin "3") (pinfunction "+IN_3") (pintype "input"))
      (node (ref "IC10") (pin "5") (pinfunction "+IN_5") (pintype "input"))
      (node (ref "IC11") (pin "1") (pinfunction "C_1") (pintype "passive"))
      (node (ref "IC12") (pin "2") (pinfunction "A_2") (pintype "passive"))
      (node (ref "IC2") (pin "1") (pinfunction "GND_1") (pintype "power_in"))
      (node (ref "IC3") (pin "2") (pinfunction "A_2") (pintype "passive"))
      (node (ref "IC4") (pin "10") (pinfunction "+IN_10") (pintype "input"))
      (node (ref "IC4") (pin "11") (pinfunction "V-_11") (pintype "power_in"))
      (node (ref "IC4") (pin "12") (pinfunction "+IN_12") (pintype "input"))
      (node (ref "IC4") (pin "3") (pinfunction "+IN_3") (pintype "input"))
      (node (ref "IC4") (pin "5") (pinfunction "+IN_5") (pintype "input"))
      (node (ref "IC5") (pin "3") (pinfunction "+IN_3") (pintype "input"))
      (node (ref "IC5") (pin "5") (pinfunction "+IN_5") (pintype "input"))
      (node (ref "IC6") (pin "3") (pinfunction "+IN_3") (pintype "input"))
      (node (ref "IC6") (pin "5") (pinfunction "+IN_5") (pintype "input"))
      (node (ref "IC7") (pin "3") (pinfunction "+IN_3") (pintype "input"))
      (node (ref "IC7") (pin "5") (pinfunction "+IN_5") (pintype "input"))
      (node (ref "IC8") (pin "8") (pinfunction "GND_8") (pintype "power_in"))
      (node (ref "IC9") (pin "8") (pinfunction "GND_8") (pintype "power_in"))
      (node (ref "J1") (pin "GND") (pinfunction "1_GND") (pintype "passive"))
      (node (ref "J1") (pin "GND2") (pinfunction "4_GND2") (pintype "passive"))
      (node (ref "J2") (pin "GND") (pinfunction "1_GND") (pintype "passive"))
      (node (ref "J2") (pin "GND2") (pinfunction "4_GND2") (pintype "passive"))
      (node (ref "J3") (pin "GND") (pinfunction "1_GND") (pintype "passive"))
      (node (ref "J3") (pin "GND2") (pinfunction "4_GND2") (pintype "passive"))
      (node (ref "J4") (pin "GND") (pinfunction "1_GND") (pintype "passive"))
      (node (ref "J4") (pin "GND2") (pinfunction "4_GND2") (pintype "passive"))
      (node (ref "J5") (pin "GND") (pinfunction "1_GND") (pintype "passive"))
      (node (ref "J5") (pin "GND2") (pinfunction "4_GND2") (pintype "passive"))
      (node (ref "J6") (pin "GND") (pinfunction "1_GND") (pintype "passive"))
      (node (ref "J6") (pin "GND2") (pinfunction "4_GND2") (pintype "passive"))
      (node (ref "J7") (pin "GND") (pinfunction "1_GND") (pintype "passive"))
      (node (ref "J7") (pin "GND2") (pinfunction "4_GND2") (pintype "passive"))
      (node (ref "J8") (pin "GND") (pinfunction "1_GND") (pintype "passive"))
      (node (ref "J8") (pin "GND2") (pinfunction "4_GND2") (pintype "passive"))
      (node (ref "JP3") (pin "2") (pinfunction "2_2") (pintype "passive"))
      (node (ref "JP6") (pin "3") (pinfunction "3_3") (pintype "passive"))
      (node (ref "JP6") (pin "4") (pinfunction "4_4") (pintype "passive"))
      (node (ref "JP6") (pin "5") (pinfunction "5_5") (pintype "passive"))
      (node (ref "JP6") (pin "6") (pinfunction "6_6") (pintype "passive"))
      (node (ref "JP6") (pin "7") (pinfunction "7_7") (pintype "passive"))
      (node (ref "JP6") (pin "8") (pinfunction "8_8") (pintype "passive"))
      (node (ref "JP7") (pin "3") (pinfunction "3_3") (pintype "passive"))
      (node (ref "JP7") (pin "5") (pinfunction "5_5") (pintype "passive"))
      (node (ref "JP7") (pin "9") (pinfunction "9_9") (pintype "passive"))
      (node (ref "R14") (pin "P$3") (pinfunction "A_P$3") (pintype "passive"))
      (node (ref "R15") (pin "P$3") (pinfunction "A_P$3") (pintype "passive"))
      (node (ref "R2") (pin "P$3") (pinfunction "A_P$3") (pintype "passive"))
      (node (ref "R3") (pin "P$3") (pinfunction "A_P$3") (pintype "passive"))
      (node (ref "R31") (pin "1") (pinfunction "1_1") (pintype "passive"))
      (node (ref "R32") (pin "P$3") (pinfunction "A_P$3") (pintype "passive"))
      (node (ref "R33") (pin "P$3") (pinfunction "A_P$3") (pintype "passive"))
      (node (ref "R45") (pin "1") (pinfunction "1_1") (pintype "passive"))
      (node (ref "SW1") (pin "1") (pinfunction "1_1") (pintype "passive"))
      (node (ref "SW1") (pin "2") (pinfunction "2_2") (pintype "passive"))
      (node (ref "SW2") (pin "1") (pinfunction "1_1") (pintype "passive"))
      (node (ref "SW2") (pin "2") (pinfunction "2_2") (pintype "passive"))
      (node (ref "SW3") (pin "1") (pinfunction "1_1") (pintype "passive"))
      (node (ref "SW3") (pin "2") (pinfunction "2_2") (pintype "passive"))
      (node (ref "UC1") (pin "20") (pinfunction "PB2/BOOT1_20") (pintype "bidirectional"))
      (node (ref "UC1") (pin "23") (pinfunction "VSS_1_23") (pintype "power_in"))
      (node (ref "UC1") (pin "35") (pinfunction "VSS_2_35") (pintype "power_in"))
      (node (ref "UC1") (pin "44") (pinfunction "BOOT0_44") (pintype "input"))
      (node (ref "UC1") (pin "47") (pinfunction "VSS_3_47") (pintype "power_in"))
      (node (ref "UC1") (pin "8") (pinfunction "VSS_A_8") (pintype "power_in"))
    )
    (net (code "23") (name "JTCK") (class "Default")
      (node (ref "JP7") (pin "4") (pinfunction "4_4") (pintype "passive"))
      (node (ref "UC1") (pin "37") (pinfunction "PA14/JTCK/SWCLK_37") (pintype "bidirectional"))
    )
    (net (code "24") (name "JTDI") (class "Default")
      (node (ref "JP7") (pin "8") (pinfunction "8_8") (pintype "passive"))
      (node (ref "UC1") (pin "38") (pinfunction "PA15/JTDI_38") (pintype "bidirectional"))
    )
    (net (code "25") (name "JTDO") (class "Default")
      (node (ref "JP7") (pin "6") (pinfunction "6_6") (pintype "passive"))
      (node (ref "UC1") (pin "39") (pinfunction "PB3/JTDO_39") (pintype "bidirectional"))
    )
    (net (code "26") (name "JTMS") (class "Default")
      (node (ref "JP7") (pin "2") (pinfunction "2_2") (pintype "passive"))
      (node (ref "UC1") (pin "34") (pinfunction "PA13/JTMS/SWDIO_34") (pintype "bidirectional"))
    )
    (net (code "27") (name "Net-(C20-Pad1)") (class "Default")
      (node (ref "C20") (pin "1") (pinfunction "1_1") (pintype "passive"))
      (node (ref "R16") (pin "2") (pinfunction "2_2") (pintype "passive"))
      (node (ref "R20") (pin "1") (pinfunction "1_1") (pintype "passive"))
    )
    (net (code "28") (name "Net-(C21-Pad1)") (class "Default")
      (node (ref "C21") (pin "1") (pinfunction "1_1") (pintype "passive"))
      (node (ref "R17") (pin "2") (pinfunction "2_2") (pintype "passive"))
      (node (ref "R21") (pin "1") (pinfunction "1_1") (pintype "passive"))
    )
    (net (code "29") (name "Net-(C36-Pad1)") (class "Default")
      (node (ref "C36") (pin "1") (pinfunction "1_1") (pintype "passive"))
      (node (ref "R41") (pin "1") (pinfunction "1_1") (pintype "passive"))
    )
    (net (code "30") (name "Net-(C37-Pad1)") (class "Default")
      (node (ref "C37") (pin "1") (pinfunction "1_1") (pintype "passive"))
      (node (ref "R40") (pin "1") (pinfunction "1_1") (pintype "passive"))
    )
    (net (code "31") (name "Net-(C38-Pad1)") (class "Default")
      (node (ref "C38") (pin "1") (pinfunction "1_1") (pintype "passive"))
      (node (ref "R38") (pin "1") (pinfunction "1_1") (pintype "passive"))
    )
    (net (code "32") (name "Net-(C42-Pad1)") (class "Default")
      (node (ref "C42") (pin "1") (pinfunction "1_1") (pintype "passive"))
      (node (ref "R43") (pin "1") (pinfunction "1_1") (pintype "passive"))
    )
    (net (code "33") (name "Net-(C50-Pad1)") (class "Default")
      (node (ref "C50") (pin "1") (pinfunction "1_1") (pintype "passive"))
      (node (ref "R47") (pin "1") (pinfunction "1_1") (pintype "passive"))
    )
    (net (code "34") (name "Net-(C51-Pad1)") (class "Default")
      (node (ref "C51") (pin "1") (pinfunction "1_1") (pintype "passive"))
      (node (ref "R48") (pin "1") (pinfunction "1_1") (pintype "passive"))
    )
    (net (code "35") (name "Net-(C54-Pad1)") (class "Default")
      (node (ref "C54") (pin "1") (pinfunction "1_1") (pintype "passive"))
      (node (ref "R50") (pin "1") (pinfunction "1_1") (pintype "passive"))
    )
    (net (code "36") (name "Net-(C55-Pad1)") (class "Default")
      (node (ref "C55") (pin "1") (pinfunction "1_1") (pintype "passive"))
      (node (ref "R55") (pin "1") (pinfunction "1_1") (pintype "passive"))
    )
    (net (code "37") (name "Net-(D3-PadA)") (class "Default")
      (node (ref "D3") (pin "A") (pinfunction "A_A") (pintype "passive"))
      (node (ref "JP6") (pin "1") (pinfunction "1_1") (pintype "passive"))
      (node (ref "JP6") (pin "2") (pinfunction "2_2") (pintype "passive"))
    )
    (net (code "38") (name "Net-(IC1-OUTA)") (class "Default")
      (node (ref "IC1") (pin "4") (pinfunction "OUTA_4") (pintype "output"))
      (node (ref "R17") (pin "1") (pinfunction "1_1") (pintype "passive"))
    )
    (net (code "39") (name "Net-(IC1-OUTB)") (class "Default")
      (node (ref "IC1") (pin "3") (pinfunction "OUTB_3") (pintype "input"))
      (node (ref "R16") (pin "1") (pinfunction "1_1") (pintype "passive"))
    )
    (net (code "40") (name "Net-(IC2-VIN)") (class "Default")
      (node (ref "C16") (pin "+") (pinfunction "+_+") (pintype "passive"))
      (node (ref "IC2") (pin "3") (pinfunction "VIN_3") (pintype "input"))
      (node (ref "R11") (pin "2") (pinfunction "2_2") (pintype "passive"))
    )
    (net (code "41") (name "Net-(IC4A--IN)") (class "Default")
      (node (ref "C26") (pin "1") (pinfunction "1_1") (pintype "passive"))
      (node (ref "IC4") (pin "2") (pinfunction "-IN_2") (pintype "input"))
      (node (ref "R22") (pin "1") (pinfunction "1_1") (pintype "passive"))
      (node (ref "R25") (pin "2") (pinfunction "2_2") (pintype "passive"))
      (node (ref "R26") (pin "2") (pinfunction "2_2") (pintype "passive"))
    )
    (net (code "42") (name "Net-(IC4B--IN)") (class "Default")
      (node (ref "C27") (pin "1") (pinfunction "1_1") (pintype "passive"))
      (node (ref "IC4") (pin "6") (pinfunction "-IN_6") (pintype "input"))
      (node (ref "R23") (pin "1") (pinfunction "1_1") (pintype "passive"))
      (node (ref "R24") (pin "2") (pinfunction "2_2") (pintype "passive"))
      (node (ref "R28") (pin "2") (pinfunction "2_2") (pintype "passive"))
    )
    (net (code "43") (name "Net-(IC4C--IN)") (class "Default")
      (node (ref "C19") (pin "1") (pinfunction "1_1") (pintype "passive"))
      (node (ref "IC4") (pin "9") (pinfunction "-IN_9") (pintype "input"))
      (node (ref "R10") (pin "2") (pinfunction "2_2") (pintype "passive"))
      (node (ref "R13") (pin "2") (pinfunction "2_2") (pintype "passive"))
      (node (ref "R19") (pin "1") (pinfunction "1_1") (pintype "passive"))
    )
    (net (code "44") (name "Net-(IC4D--IN)") (class "Default")
      (node (ref "C18") (pin "1") (pinfunction "1_1") (pintype "passive"))
      (node (ref "IC4") (pin "13") (pinfunction "-IN_13") (pintype "input"))
      (node (ref "R12") (pin "2") (pinfunction "2_2") (pintype "passive"))
      (node (ref "R18") (pin "1") (pinfunction "1_1") (pintype "passive"))
      (node (ref "R9") (pin "2") (pinfunction "2_2") (pintype "passive"))
    )
    (net (code "45") (name "Net-(IC5A--IN)") (class "Default")
      (node (ref "IC5") (pin "1") (pinfunction "OUT_1") (pintype "output"))
      (node (ref "IC5") (pin "2") (pinfunction "-IN_2") (pintype "input"))
    )
    (net (code "46") (name "Net-(IC5B--IN)") (class "Default")
      (node (ref "C30") (pin "1") (pinfunction "1_1") (pintype "passive"))
      (node (ref "IC5") (pin "6") (pinfunction "-IN_6") (pintype "input"))
      (node (ref "IC8") (pin "12") (pinfunction "OUT_12") (pintype "output"))
      (node (ref "R30") (pin "2") (pinfunction "2_2") (pintype "passive"))
      (node (ref "R32") (pin "P$1") (pinfunction "E_P$1") (pintype "passive"))
      (node (ref "R65") (pin "2") (pinfunction "2_2") (pintype "passive"))
    )
    (net (code "47") (name "Net-(IC6A--IN)") (class "Default")
      (node (ref "IC6") (pin "1") (pinfunction "OUT_1") (pintype "output"))
      (node (ref "IC6") (pin "2") (pinfunction "-IN_2") (pintype "input"))
    )
    (net (code "48") (name "Net-(IC6B--IN)") (class "Default")
      (node (ref "C31") (pin "1") (pinfunction "1_1") (pintype "passive"))
      (node (ref "IC6") (pin "6") (pinfunction "-IN_6") (pintype "input"))
      (node (ref "IC9") (pin "13") (pinfunction "OUT_13") (pintype "output"))
      (node (ref "R29") (pin "2") (pinfunction "2_2") (pintype "passive"))
      (node (ref "R33") (pin "P$1") (pinfunction "E_P$1") (pintype "passive"))
      (node (ref "R64") (pin "2") (pinfunction "2_2") (pintype "passive"))
    )
    (net (code "49") (name "Net-(IC7A--IN)") (class "Default")
      (node (ref "C53") (pin "1") (pinfunction "1_1") (pintype "passive"))
      (node (ref "IC7") (pin "2") (pinfunction "-IN_2") (pintype "input"))
      (node (ref "IC8") (pin "4") (pinfunction "OUT_4") (pintype "output"))
    )
    (net (code "50") (name "Net-(IC7A-OUT)") (class "Default")
      (node (ref "C53") (pin "2") (pinfunction "2_2") (pintype "passive"))
      (node (ref "IC7") (pin "1") (pinfunction "OUT_1") (pintype "output"))
      (node (ref "R49") (pin "2") (pinfunction "2_2") (pintype "passive"))
      (node (ref "R51") (pin "1") (pinfunction "1_1") (pintype "passive"))
    )
    (net (code "51") (name "Net-(IC7B--IN)") (class "Default")
      (node (ref "C40") (pin "1") (pinfunction "1_1") (pintype "passive"))
      (node (ref "IC7") (pin "6") (pinfunction "-IN_6") (pintype "input"))
      (node (ref "IC8") (pin "5") (pinfunction "OUT_5") (pintype "output"))
    )
    (net (code "52") (name "Net-(IC7B-OUT)") (class "Default")
      (node (ref "C40") (pin "2") (pinfunction "2_2") (pintype "passive"))
      (node (ref "IC7") (pin "7") (pinfunction "OUT_7") (pintype "output"))
      (node (ref "R52") (pin "2") (pinfunction "2_2") (pintype "passive"))
      (node (ref "R61") (pin "1") (pinfunction "1_1") (pintype "passive"))
    )
    (net (code "53") (name "Net-(IC8A-IN)") (class "Default")
      (node (ref "IC8") (pin "13") (pinfunction "OUT_13") (pintype "output"))
      (node (ref "IC8") (pin "2") (pinfunction "IN_2") (pintype "input"))
      (node (ref "R49") (pin "1") (pinfunction "1_1") (pintype "passive"))
      (node (ref "R50") (pin "2") (pinfunction "2_2") (pintype "passive"))
    )
    (net (code "54") (name "Net-(IC8B-IN)") (class "Default")
      (node (ref "IC8") (pin "7") (pinfunction "IN_7") (pintype "input"))
      (node (ref "R47") (pin "2") (pinfunction "2_2") (pintype "passive"))
      (node (ref "R51") (pin "2") (pinfunction "2_2") (pintype "passive"))
      (node (ref "R52") (pin "1") (pinfunction "1_1") (pintype "passive"))
    )
    (net (code "55") (name "Net-(IC8C-CTRL)") (class "Default")
      (node (ref "IC8") (pin "11") (pinfunction "CTRL_11") (pintype "input"))
      (node (ref "R27") (pin "P$2") (pinfunction "S_P$2") (pintype "passive"))
    )
    (net (code "56") (name "Net-(IC8C-IN)") (class "Default")
      (node (ref "IC8") (pin "10") (pinfunction "IN_10") (pintype "input"))
      (node (ref "R37") (pin "2") (pinfunction "2_2") (pintype "passive"))
      (node (ref "R38") (pin "2") (pinfunction "2_2") (pintype "passive"))
    )
    (net (code "57") (name "Net-(IC8D-IN)") (class "Default")
      (node (ref "IC8") (pin "15") (pinfunction "IN_15") (pintype "input"))
      (node (ref "R41") (pin "2") (pinfunction "2_2") (pintype "passive"))
      (node (ref "R42") (pin "2") (pinfunction "2_2") (pintype "passive"))
    )
    (net (code "58") (name "Net-(IC9A-IN)") (class "Default")
      (node (ref "IC9") (pin "2") (pinfunction "IN_2") (pintype "input"))
      (node (ref "R48") (pin "2") (pinfunction "2_2") (pintype "passive"))
      (node (ref "R53") (pin "1") (pinfunction "1_1") (pintype "passive"))
      (node (ref "R54") (pin "2") (pinfunction "2_2") (pintype "passive"))
    )
    (net (code "59") (name "Net-(IC9B-IN)") (class "Default")
      (node (ref "IC9") (pin "12") (pinfunction "OUT_12") (pintype "output"))
      (node (ref "IC9") (pin "7") (pinfunction "IN_7") (pintype "input"))
      (node (ref "R55") (pin "2") (pinfunction "2_2") (pintype "passive"))
      (node (ref "R56") (pin "1") (pinfunction "1_1") (pintype "passive"))
    )
    (net (code "60") (name "Net-(IC9C-IN)") (class "Default")
      (node (ref "IC9") (pin "10") (pinfunction "IN_10") (pintype "input"))
      (node (ref "R39") (pin "2") (pinfunction "2_2") (pintype "passive"))
      (node (ref "R40") (pin "2") (pinfunction "2_2") (pintype "passive"))
    )
    (net (code "61") (name "Net-(IC9D-CTRL)") (class "Default")
      (node (ref "IC9") (pin "14") (pinfunction "CTRL_14") (pintype "input"))
      (node (ref "R36") (pin "P$2") (pinfunction "S_P$2") (pintype "passive"))
    )
    (net (code "62") (name "Net-(IC9D-IN)") (class "Default")
      (node (ref "IC9") (pin "15") (pinfunction "IN_15") (pintype "input"))
      (node (ref "R43") (pin "2") (pinfunction "2_2") (pintype "passive"))
      (node (ref "R44") (pin "2") (pinfunction "2_2") (pintype "passive"))
    )
    (net (code "63") (name "Net-(IC10A--IN)") (class "Default")
      (node (ref "C52") (pin "1") (pinfunction "1_1") (pintype "passive"))
      (node (ref "IC10") (pin "2") (pinfunction "-IN_2") (pintype "input"))
      (node (ref "IC9") (pin "5") (pinfunction "OUT_5") (pintype "output"))
    )
    (net (code "64") (name "Net-(IC10A-OUT)") (class "Default")
      (node (ref "C52") (pin "2") (pinfunction "2_2") (pintype "passive"))
      (node (ref "IC10") (pin "1") (pinfunction "OUT_1") (pintype "output"))
      (node (ref "R54") (pin "1") (pinfunction "1_1") (pintype "passive"))
      (node (ref "R56") (pin "2") (pinfunction "2_2") (pintype "passive"))
    )
    (net (code "65") (name "Net-(IC10B--IN)") (class "Default")
      (node (ref "C43") (pin "1") (pinfunction "1_1") (pintype "passive"))
      (node (ref "IC10") (pin "6") (pinfunction "-IN_6") (pintype "input"))
      (node (ref "IC9") (pin "4") (pinfunction "OUT_4") (pintype "output"))
    )
    (net (code "66") (name "Net-(IC10B-OUT)") (class "Default")
      (node (ref "C43") (pin "2") (pinfunction "2_2") (pintype "passive"))
      (node (ref "IC10") (pin "7") (pinfunction "OUT_7") (pintype "output"))
      (node (ref "R53") (pin "2") (pinfunction "2_2") (pintype "passive"))
      (node (ref "R62") (pin "1") (pinfunction "1_1") (pintype "passive"))
    )
    (net (code "67") (name "Net-(J1-2)") (class "Default")
      (node (ref "J1") (pin "TIP") (pinfunction "2_TIP") (pintype "passive"))
      (node (ref "R25") (pin "1") (pinfunction "1_1") (pintype "passive"))
    )
    (net (code "68") (name "Net-(J2-2)") (class "Default")
      (node (ref "J2") (pin "TIP") (pinfunction "2_TIP") (pintype "passive"))
      (node (ref "R12") (pin "1") (pinfunction "1_1") (pintype "passive"))
      (node (ref "R42") (pin "1") (pinfunction "1_1") (pintype "passive"))
    )
    (net (code "69") (name "Net-(J2-3)") (class "Default")
      (node (ref "J2") (pin "SW") (pinfunction "3_SW") (pintype "passive"))
      (node (ref "R59") (pin "1") (pinfunction "1_1") (pintype "passive"))
    )
    (net (code "70") (name "Net-(J3-2)") (class "Default")
      (node (ref "J3") (pin "TIP") (pinfunction "2_TIP") (pintype "passive"))
      (node (ref "R13") (pin "1") (pinfunction "1_1") (pintype "passive"))
      (node (ref "R39") (pin "1") (pinfunction "1_1") (pintype "passive"))
    )
    (net (code "71") (name "Net-(J3-3)") (class "Default")
      (node (ref "J3") (pin "SW") (pinfunction "3_SW") (pintype "passive"))
      (node (ref "R58") (pin "1") (pinfunction "1_1") (pintype "passive"))
    )
    (net (code "72") (name "Net-(J4-2)") (class "Default")
      (node (ref "J4") (pin "TIP") (pinfunction "2_TIP") (pintype "passive"))
      (node (ref "R28") (pin "1") (pinfunction "1_1") (pintype "passive"))
    )
    (net (code "73") (name "Net-(J5-2)") (class "Default")
      (node (ref "J5") (pin "TIP") (pinfunction "2_TIP") (pintype "passive"))
      (node (ref "R34") (pin "1") (pinfunction "1_1") (pintype "passive"))
    )
    (net (code "74") (name "Net-(J5-3)") (class "Default")
      (node (ref "J5") (pin "SW") (pinfunction "3_SW") (pintype "passive"))
      (node (ref "R60") (pin "1") (pinfunction "1_1") (pintype "passive"))
    )
    (net (code "75") (name "Net-(J6-2)") (class "Default")
      (node (ref "J6") (pin "TIP") (pinfunction "2_TIP") (pintype "passive"))
      (node (ref "R61") (pin "2") (pinfunction "2_2") (pintype "passive"))
    )
    (net (code "76") (name "Net-(J7-2)") (class "Default")
      (node (ref "J7") (pin "TIP") (pinfunction "2_TIP") (pintype "passive"))
      (node (ref "R62") (pin "2") (pinfunction "2_2") (pintype "passive"))
    )
    (net (code "77") (name "Net-(J8-2)") (class "Default")
      (node (ref "J8") (pin "TIP") (pinfunction "2_TIP") (pintype "passive"))
      (node (ref "R35") (pin "1") (pinfunction "1_1") (pintype "passive"))
    )
    (net (code "78") (name "Net-(J8-3)") (class "Default")
      (node (ref "J8") (pin "SW") (pinfunction "3_SW") (pintype "passive"))
      (node (ref "R63") (pin "1") (pinfunction "1_1") (pintype "passive"))
    )
    (net (code "79") (name "Net-(JP6-Pad10)") (class "Default")
      (node (ref "JP6") (pin "10") (pinfunction "10_10") (pintype "passive"))
      (node (ref "JP6") (pin "9") (pinfunction "9_9") (pintype "passive"))
      (node (ref "P1") (pin "2") (pinfunction "2_2") (pintype "bidirectional"))
    )
    (net (code "80") (name "Net-(R27-A)") (class "Default")
      (node (ref "R27") (pin "P$3") (pinfunction "A_P$3") (pintype "passive"))
      (node (ref "R31") (pin "2") (pinfunction "2_2") (pintype "passive"))
    )
    (net (code "81") (name "Net-(R32-S)") (class "Default")
      (node (ref "R32") (pin "P$2") (pinfunction "S_P$2") (pintype "passive"))
      (node (ref "R34") (pin "2") (pinfunction "2_2") (pintype "passive"))
    )
    (net (code "82") (name "Net-(R33-S)") (class "Default")
      (node (ref "R33") (pin "P$2") (pinfunction "S_P$2") (pintype "passive"))
      (node (ref "R35") (pin "2") (pinfunction "2_2") (pintype "passive"))
    )
    (net (code "83") (name "Net-(R36-A)") (class "Default")
      (node (ref "R36") (pin "P$3") (pinfunction "A_P$3") (pintype "passive"))
      (node (ref "R45") (pin "2") (pinfunction "2_2") (pintype "passive"))
    )
    (net (code "84") (name "Net-(UC1-PA10{slash}USART1_RX{slash}TIM1_CH3)") (class "Default")
      (node (ref "R4") (pin "1") (pinfunction "1_1") (pintype "passive"))
      (node (ref "UC1") (pin "31") (pinfunction "PA10/USART1_RX/TIM1_CH3_31") (pintype "bidirectional"))
    )
    (net (code "85") (name "Net-(UC1-PA11{slash}USART1_CTS{slash}CAN_RX{slash}TIM1_CH4{slash}USBDM)") (class "Default")
      (node (ref "R5") (pin "1") (pinfunction "1_1") (pintype "passive"))
      (node (ref "UC1") (pin "32") (pinfunction "PA11/USART1_CTS/CAN_RX/TIM1_CH4/USBDM_32") (pintype "bidirectional"))
    )
    (net (code "86") (name "Net-(UC1-PD0-OSC_IN)") (class "Default")
      (node (ref "C5") (pin "2") (pinfunction "2_2") (pintype "passive"))
      (node (ref "Q1") (pin "2") (pinfunction "2_2") (pintype "passive"))
      (node (ref "UC1") (pin "5") (pinfunction "PD0-OSC_IN_5") (pintype "input"))
    )
    (net (code "87") (name "Net-(UC1-PD1-OSC_OUT)") (class "Default")
      (node (ref "C12") (pin "2") (pinfunction "2_2") (pintype "passive"))
      (node (ref "Q1") (pin "1") (pinfunction "1_1") (pintype "passive"))
      (node (ref "UC1") (pin "6") (pinfunction "PD1-OSC_OUT_6") (pintype "input"))
    )
    (net (code "88") (name "PWM_CUTOFF_1") (class "Default")
      (node (ref "C6") (pin "1") (pinfunction "1_1") (pintype "passive"))
      (node (ref "IC8") (pin "3") (pinfunction "CTRL_3") (pintype "input"))
      (node (ref "IC8") (pin "6") (pinfunction "CTRL_6") (pintype "input"))
      (node (ref "R4") (pin "2") (pinfunction "2_2") (pintype "passive"))
    )
    (net (code "89") (name "PWM_CUTOFF_2") (class "Default")
      (node (ref "C7") (pin "1") (pinfunction "1_1") (pintype "passive"))
      (node (ref "IC9") (pin "3") (pinfunction "CTRL_3") (pintype "input"))
      (node (ref "IC9") (pin "6") (pinfunction "CTRL_6") (pintype "input"))
      (node (ref "R5") (pin "2") (pinfunction "2_2") (pintype "passive"))
    )
    (net (code "90") (name "RESET") (class "Default")
      (node (ref "JP7") (pin "10") (pinfunction "10_10") (pintype "passive"))
      (node (ref "R1") (pin "1") (pinfunction "1_1") (pintype "passive"))
      (node (ref "UC1") (pin "7") (pinfunction "NRST_7") (pintype "input"))
    )
    (net (code "91") (name "SHAPE_1") (class "Default")
      (node (ref "R2") (pin "P$2") (pinfunction "S_P$2") (pintype "passive"))
      (node (ref "UC1") (pin "12") (pinfunction "PA2/USART2_TX/ADC12_IN2/TIM2_CH3_12") (pintype "bidirectional"))
    )
    (net (code "92") (name "SHAPE_2") (class "Default")
      (node (ref "R3") (pin "P$2") (pinfunction "S_P$2") (pintype "passive"))
      (node (ref "UC1") (pin "11") (pinfunction "PA1/USART2_RTS/ADC12_IN1/TIM2_CH2_11") (pintype "bidirectional"))
    )
    (net (code "93") (name "SW_METER") (class "Default")
      (node (ref "SW3") (pin "3") (pinfunction "3_3") (pintype "passive"))
      (node (ref "SW3") (pin "4") (pinfunction "4_4") (pintype "passive"))
      (node (ref "UC1") (pin "42") (pinfunction "PB6/I2C1_SCL/TIM4_CH1_42") (pintype "input"))
    )
    (net (code "94") (name "SW_MODE_1") (class "Default")
      (node (ref "SW1") (pin "3") (pinfunction "3_3") (pintype "passive"))
      (node (ref "SW1") (pin "4") (pinfunction "4_4") (pintype "passive"))
      (node (ref "UC1") (pin "41") (pinfunction "PB5/I2C1_SMBA_41") (pintype "input"))
    )
    (net (code "95") (name "SW_MODE_2") (class "Default")
      (node (ref "SW2") (pin "3") (pinfunction "3_3") (pintype "passive"))
      (node (ref "SW2") (pin "4") (pinfunction "4_4") (pintype "passive"))
      (node (ref "UC1") (pin "40") (pinfunction "PB4/NJTRST_40") (pintype "bidirectional"))
    )
    (net (code "96") (name "VCA_CONTROL_1") (class "Default")
      (node (ref "C30") (pin "2") (pinfunction "2_2") (pintype "passive"))
      (node (ref "D5") (pin "C") (pinfunction "C_C") (pintype "passive"))
      (node (ref "IC5") (pin "7") (pinfunction "OUT_7") (pintype "output"))
      (node (ref "IC8") (pin "14") (pinfunction "CTRL_14") (pintype "input"))
      (node (ref "R27") (pin "P$1") (pinfunction "E_P$1") (pintype "passive"))
      (node (ref "R6") (pin "2") (pinfunction "2_2") (pintype "passive"))
      (node (ref "TP1") (pin "P$1") (pinfunction "1_P$1") (pintype "bidirectional"))
    )
    (net (code "97") (name "VCA_CONTROL_2") (class "Default")
      (node (ref "C31") (pin "2") (pinfunction "2_2") (pintype "passive"))
      (node (ref "D4") (pin "C") (pinfunction "C_C") (pintype "passive"))
      (node (ref "IC6") (pin "7") (pinfunction "OUT_7") (pintype "output"))
      (node (ref "IC9") (pin "11") (pinfunction "CTRL_11") (pintype "input"))
      (node (ref "R36") (pin "P$1") (pinfunction "E_P$1") (pintype "passive"))
      (node (ref "R7") (pin "2") (pinfunction "2_2") (pintype "passive"))
      (node (ref "TP2") (pin "P$1") (pinfunction "1_P$1") (pintype "bidirectional"))
    )
    (net (code "98") (name "VCC") (class "Default")
      (node (ref "C24") (pin "+") (pinfunction "+_+") (pintype "passive"))
      (node (ref "C29") (pin "1") (pinfunction "1_1") (pintype "passive"))
      (node (ref "C32") (pin "1") (pinfunction "1_1") (pintype "passive"))
      (node (ref "C35") (pin "1") (pinfunction "1_1") (pintype "passive"))
      (node (ref "C41") (pin "1") (pinfunction "1_1") (pintype "passive"))
      (node (ref "C45") (pin "1") (pinfunction "1_1") (pintype "passive"))
      (node (ref "C46") (pin "1") (pinfunction "1_1") (pintype "passive"))
      (node (ref "D3") (pin "C") (pinfunction "C_C") (pintype "passive"))
      (node (ref "IC10") (pin "8") (pinfunction "V+_8") (pintype "power_in"))
      (node (ref "IC5") (pin "8") (pinfunction "V+_8") (pintype "power_in"))
      (node (ref "IC6") (pin "8") (pinfunction "V+_8") (pintype "power_in"))
      (node (ref "IC7") (pin "8") (pinfunction "V+_8") (pintype "power_in"))
      (node (ref "IC8") (pin "16") (pinfunction "V+_16") (pintype "power_in"))
      (node (ref "IC9") (pin "16") (pinfunction "V+_16") (pintype "power_in"))
      (node (ref "R11") (pin "1") (pinfunction "1_1") (pintype "passive"))
      (node (ref "R57") (pin "1") (pinfunction "1_1") (pintype "passive"))
    )
    (net (code "99") (name "VEE") (class "Default")
      (node (ref "C28") (pin "-") (pinfunction "-_-") (pintype "passive"))
      (node (ref "C33") (pin "2") (pinfunction "2_2") (pintype "passive"))
      (node (ref "C34") (pin "2") (pinfunction "2_2") (pintype "passive"))
      (node (ref "C39") (pin "2") (pinfunction "2_2") (pintype "passive"))
      (node (ref "C44") (pin "2") (pinfunction "2_2") (pintype "passive"))
      (node (ref "C48") (pin "2") (pinfunction "2_2") (pintype "passive"))
      (node (ref "C49") (pin "2") (pinfunction "2_2") (pintype "passive"))
      (node (ref "D6") (pin "A") (pinfunction "A_A") (pintype "passive"))
      (node (ref "IC10") (pin "4") (pinfunction "V-_4") (pintype "power_in"))
      (node (ref "IC5") (pin "4") (pinfunction "V-_4") (pintype "power_in"))
      (node (ref "IC6") (pin "4") (pinfunction "V-_4") (pintype "power_in"))
      (node (ref "IC7") (pin "4") (pinfunction "V-_4") (pintype "power_in"))
      (node (ref "IC8") (pin "9") (pinfunction "V-_9") (pintype "power_in"))
      (node (ref "IC9") (pin "9") (pinfunction "V-_9") (pintype "power_in"))
      (node (ref "P1") (pin "1") (pinfunction "1_1") (pintype "bidirectional"))
      (node (ref "R46") (pin "1") (pinfunction "1_1") (pintype "passive"))
    )
    (net (code "100") (name "unconnected-(IC8E-MODE-Pad1)") (class "Default")
      (node (ref "IC8") (pin "1") (pinfunction "MODE_1") (pintype "input"))
    )
    (net (code "101") (name "unconnected-(IC9E-MODE-Pad1)") (class "Default")
      (node (ref "IC9") (pin "1") (pinfunction "MODE_1") (pintype "input"))
    )
    (net (code "102") (name "unconnected-(J1-3-PadSW)") (class "Default")
      (node (ref "J1") (pin "SW") (pinfunction "3_SW") (pintype "passive"))
    )
    (net (code "103") (name "unconnected-(J4-3-PadSW)") (class "Default")
      (node (ref "J4") (pin "SW") (pinfunction "3_SW") (pintype "passive"))
    )
    (net (code "104") (name "unconnected-(J6-3-PadSW)") (class "Default")
      (node (ref "J6") (pin "SW") (pinfunction "3_SW") (pintype "passive"))
    )
    (net (code "105") (name "unconnected-(J7-3-PadSW)") (class "Default")
      (node (ref "J7") (pin "SW") (pinfunction "3_SW") (pintype "passive"))
    )
    (net (code "106") (name "unconnected-(JP7-Pad7)") (class "Default")
      (node (ref "JP7") (pin "7") (pinfunction "7_7") (pintype "passive"))
    )
    (net (code "107") (name "unconnected-(UC1-PA8{slash}USART1_CK{slash}TIM1_CH1{slash}MCO-Pad29)") (class "Default")
      (node (ref "UC1") (pin "29") (pinfunction "PA8/USART1_CK/TIM1_CH1/MCO_29") (pintype "bidirectional"))
    )
    (net (code "108") (name "unconnected-(UC1-PA9{slash}USART1_TX{slash}TIM1_CH2-Pad30)") (class "Default")
      (node (ref "UC1") (pin "30") (pinfunction "PA9/USART1_TX/TIM1_CH2_30") (pintype "input"))
    )
    (net (code "109") (name "unconnected-(UC1-PA12{slash}USART1_RTS{slash}CAN_TX{slash}TIM1_ETR{slash}USBDP-Pad33)") (class "Default")
      (node (ref "UC1") (pin "33") (pinfunction "PA12/USART1_RTS/CAN_TX/TIM1_ETR/USBDP_33") (pintype "bidirectional"))
    )
    (net (code "110") (name "unconnected-(UC1-PB8{slash}TIM4_CH3-Pad45)") (class "Default")
      (node (ref "UC1") (pin "45") (pinfunction "PB8/TIM4_CH3_45") (pintype "bidirectional"))
    )
    (net (code "111") (name "unconnected-(UC1-PB9{slash}TIM4_CH4-Pad46)") (class "Default")
      (node (ref "UC1") (pin "46") (pinfunction "PB9/TIM4_CH4_46") (pintype "input"))
    )
    (net (code "112") (name "unconnected-(UC1-PB14{slash}SPI2_MISO{slash}USART3_RTS{slash}TIM1_CH2N-Pad27)") (class "Default")
      (node (ref "UC1") (pin "27") (pinfunction "PB14/SPI2_MISO/USART3_RTS/TIM1_CH2N_27") (pintype "input"))
    )
    (net (code "113") (name "unconnected-(UC1-PC13-TAMPER-RTC-Pad2)") (class "Default")
      (node (ref "UC1") (pin "2") (pinfunction "PC13-TAMPER-RTC_2") (pintype "input"))
    )
    (net (code "114") (name "unconnected-(UC1-PC14-OSC32_IN-Pad3)") (class "Default")
      (node (ref "UC1") (pin "3") (pinfunction "PC14-OSC32_IN_3") (pintype "input"))
    )
    (net (code "115") (name "unconnected-(UC1-PC15-OSC32_OUT-Pad4)") (class "Default")
      (node (ref "UC1") (pin "4") (pinfunction "PC15-OSC32_OUT_4") (pintype "input"))
    )
  )
)
